# 1-Schematic_MiniMax_4bit.net
KiCad netlist of a schematic drawn in EasyEDA
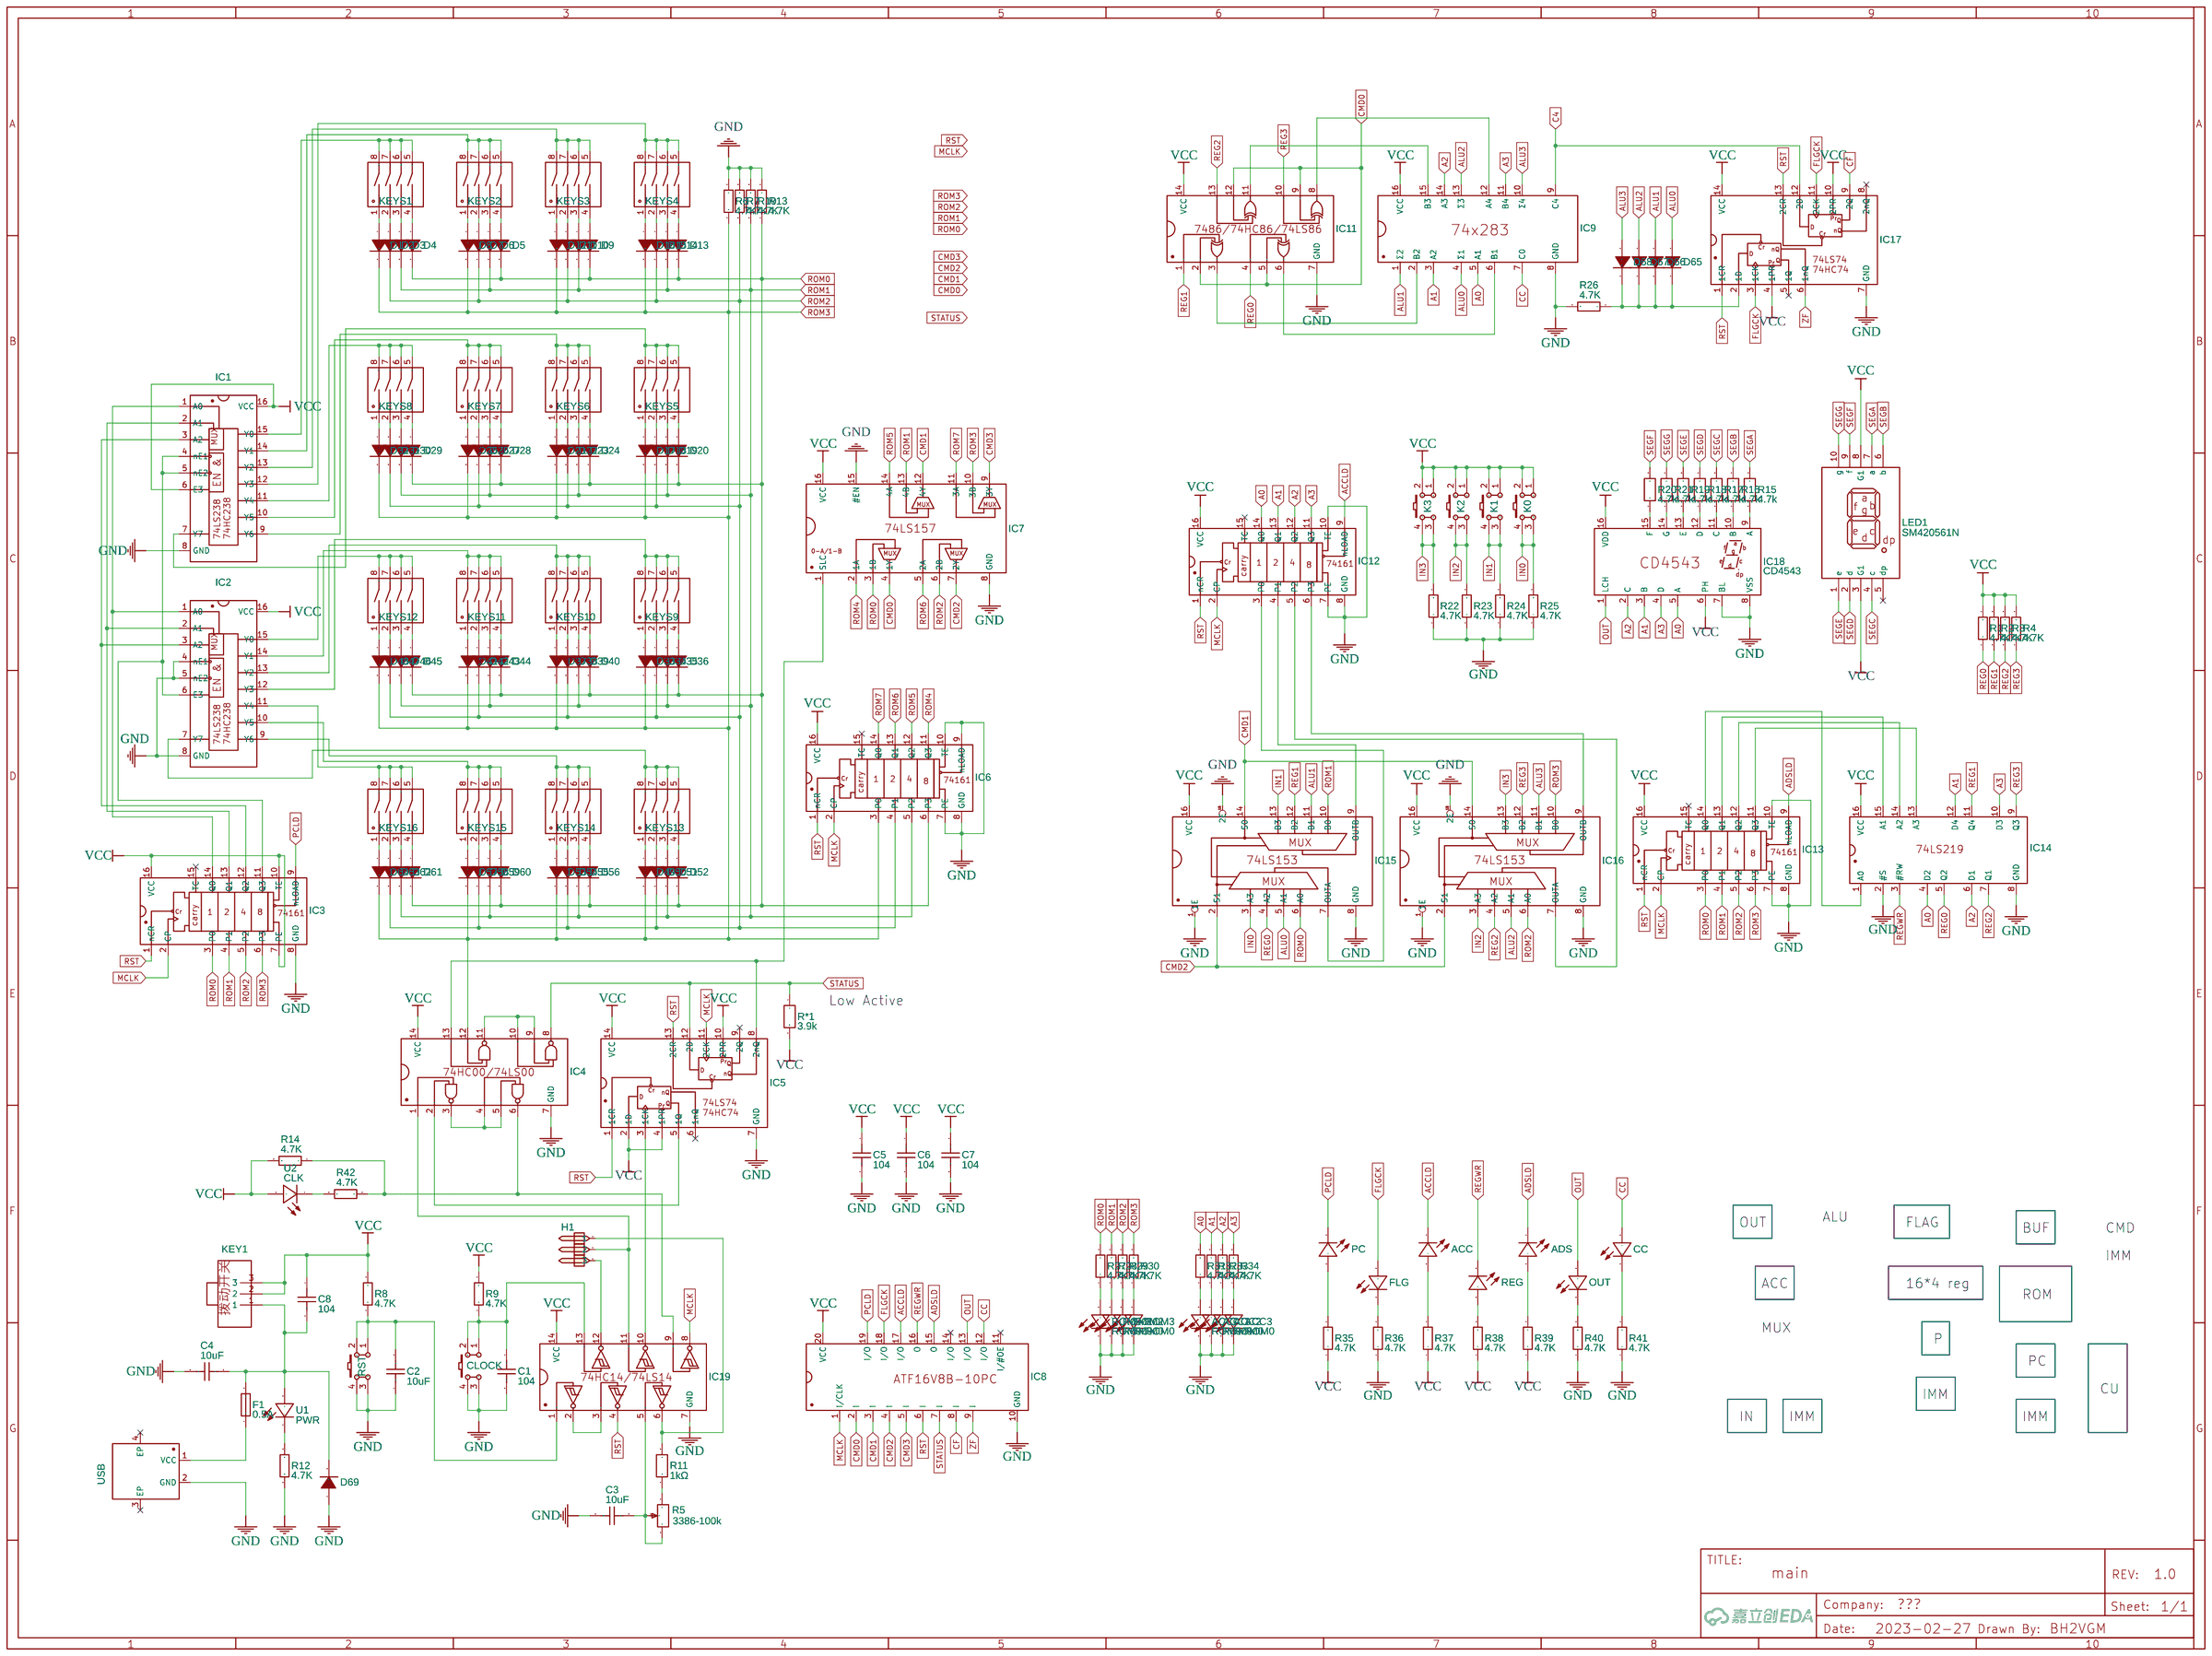
[diagram p0: schematic sheet]

(export (version "E")
  (design (tool "Eeschema 10.0.6"))
  (components
    (comp (ref "ACC")
      (value "ROM0")
      (fields
        (field (name "BOM_Manufacturer Part") "LED0805-1")
        (field (name "BOM_Supplier Part") "C9900006888")
      )
      (libsource (lib "") (part "LED0805-1_3"))
    )
    (comp (ref "ACC0")
      (value "ROM0")
      (fields
        (field (name "BOM_Manufacturer Part") "LED0805-1")
        (field (name "BOM_Supplier Part") "C9900006888")
      )
      (libsource (lib "") (part "LED0805-1_2"))
    )
    (comp (ref "ACC1")
      (value "ROM0")
      (fields
        (field (name "BOM_Manufacturer Part") "LED0805-1")
        (field (name "BOM_Supplier Part") "C9900006888")
      )
      (libsource (lib "") (part "LED0805-1_2"))
    )
    (comp (ref "ACC2")
      (value "ROM0")
      (fields
        (field (name "BOM_Manufacturer Part") "LED0805-1")
        (field (name "BOM_Supplier Part") "C9900006888")
      )
      (libsource (lib "") (part "LED0805-1_2"))
    )
    (comp (ref "ACC3")
      (value "ROM0")
      (fields
        (field (name "BOM_Manufacturer Part") "LED0805-1")
        (field (name "BOM_Supplier Part") "C9900006888")
      )
      (libsource (lib "") (part "LED0805-1_2"))
    )
    (comp (ref "ADS")
      (value "ROM0")
      (fields
        (field (name "BOM_Manufacturer Part") "LED0805-1")
        (field (name "BOM_Supplier Part") "C9900006888")
      )
      (libsource (lib "") (part "LED0805-1_1"))
    )
    (comp (ref "C1")
      (value "104")
      (fields
        (field (name "BOM_Manufacturer Part") "CC0805JRX7R7BB104")
        (field (name "BOM_Supplier Part") "C520082")
      )
      (libsource (lib "") (part "CC0805JRX7R7BB104"))
    )
    (comp (ref "C2")
      (value "10uF")
      (fields
        (field (name "BOM_Manufacturer Part") "C1206C225J5RECAUTO")
        (field (name "BOM_Supplier Part") "C1513220")
      )
      (libsource (lib "") (part "C1206C225J5RECAUTO_1"))
    )
    (comp (ref "C3")
      (value "10uF")
      (fields
        (field (name "BOM_Manufacturer Part") "C1206C225J5RECAUTO")
        (field (name "BOM_Supplier Part") "C1513220")
      )
      (libsource (lib "") (part "C1206C225J5RECAUTO_2"))
    )
    (comp (ref "C4")
      (value "10uF")
      (fields
        (field (name "BOM_Manufacturer Part") "C1206C225J5RECAUTO")
        (field (name "BOM_Supplier Part") "C1513220")
      )
      (libsource (lib "") (part "C1206C225J5RECAUTO"))
    )
    (comp (ref "C5")
      (value "104")
      (fields
        (field (name "BOM_Manufacturer Part") "CC0805JRX7R7BB104")
        (field (name "BOM_Supplier Part") "C520082")
      )
      (libsource (lib "") (part "CC0805JRX7R7BB104"))
    )
    (comp (ref "C6")
      (value "104")
      (fields
        (field (name "BOM_Manufacturer Part") "CC0805JRX7R7BB104")
        (field (name "BOM_Supplier Part") "C520082")
      )
      (libsource (lib "") (part "CC0805JRX7R7BB104"))
    )
    (comp (ref "C7")
      (value "104")
      (fields
        (field (name "BOM_Manufacturer Part") "CC0805JRX7R7BB104")
        (field (name "BOM_Supplier Part") "C520082")
      )
      (libsource (lib "") (part "CC0805JRX7R7BB104"))
    )
    (comp (ref "C8")
      (value "104")
      (fields
        (field (name "BOM_Manufacturer Part") "CC0805JRX7R7BB104")
        (field (name "BOM_Supplier Part") "C520082")
      )
      (libsource (lib "") (part "CC0805JRX7R7BB104"))
    )
    (comp (ref "CC")
      (value "ROM0")
      (fields
        (field (name "BOM_Manufacturer Part") "LED0805-1")
        (field (name "BOM_Supplier Part") "C9900006888")
      )
      (libsource (lib "") (part "LED0805-1_6"))
    )
    (comp (ref "CLOCK")
      (value "K4-6×6_TH")
      (fields
        (field (name "BOM_Manufacturer Part") "K2-1102DP-E4SW-04")
        (field (name "BOM_Supplier Part") "C136684")
      )
      (libsource (lib "") (part "K4-6×6_TH"))
    )
    (comp (ref "D1")
      (value "LL4148SG")
      (fields (field (name "BOM_Supplier Part") "C9900015421"))
      (libsource (lib "") (part "LL4148SG"))
    )
    (comp (ref "D2")
      (value "LL4148SG")
      (fields (field (name "BOM_Supplier Part") "C9900015421"))
      (libsource (lib "") (part "LL4148SG"))
    )
    (comp (ref "D3")
      (value "LL4148SG")
      (fields (field (name "BOM_Supplier Part") "C9900015421"))
      (libsource (lib "") (part "LL4148SG"))
    )
    (comp (ref "D4")
      (value "LL4148SG")
      (fields (field (name "BOM_Supplier Part") "C9900015421"))
      (libsource (lib "") (part "LL4148SG"))
    )
    (comp (ref "D5")
      (value "LL4148SG")
      (fields (field (name "BOM_Supplier Part") "C9900015421"))
      (libsource (lib "") (part "LL4148SG"))
    )
    (comp (ref "D6")
      (value "LL4148SG")
      (fields (field (name "BOM_Supplier Part") "C9900015421"))
      (libsource (lib "") (part "LL4148SG"))
    )
    (comp (ref "D7")
      (value "LL4148SG")
      (fields (field (name "BOM_Supplier Part") "C9900015421"))
      (libsource (lib "") (part "LL4148SG"))
    )
    (comp (ref "D8")
      (value "LL4148SG")
      (fields (field (name "BOM_Supplier Part") "C9900015421"))
      (libsource (lib "") (part "LL4148SG"))
    )
    (comp (ref "D9")
      (value "LL4148SG")
      (fields (field (name "BOM_Supplier Part") "C9900015421"))
      (libsource (lib "") (part "LL4148SG"))
    )
    (comp (ref "D10")
      (value "LL4148SG")
      (fields (field (name "BOM_Supplier Part") "C9900015421"))
      (libsource (lib "") (part "LL4148SG"))
    )
    (comp (ref "D11")
      (value "LL4148SG")
      (fields (field (name "BOM_Supplier Part") "C9900015421"))
      (libsource (lib "") (part "LL4148SG"))
    )
    (comp (ref "D12")
      (value "LL4148SG")
      (fields (field (name "BOM_Supplier Part") "C9900015421"))
      (libsource (lib "") (part "LL4148SG"))
    )
    (comp (ref "D13")
      (value "LL4148SG")
      (fields (field (name "BOM_Supplier Part") "C9900015421"))
      (libsource (lib "") (part "LL4148SG"))
    )
    (comp (ref "D14")
      (value "LL4148SG")
      (fields (field (name "BOM_Supplier Part") "C9900015421"))
      (libsource (lib "") (part "LL4148SG"))
    )
    (comp (ref "D15")
      (value "LL4148SG")
      (fields (field (name "BOM_Supplier Part") "C9900015421"))
      (libsource (lib "") (part "LL4148SG"))
    )
    (comp (ref "D16")
      (value "LL4148SG")
      (fields (field (name "BOM_Supplier Part") "C9900015421"))
      (libsource (lib "") (part "LL4148SG"))
    )
    (comp (ref "D17")
      (value "LL4148SG")
      (fields (field (name "BOM_Supplier Part") "C9900015421"))
      (libsource (lib "") (part "LL4148SG"))
    )
    (comp (ref "D18")
      (value "LL4148SG")
      (fields (field (name "BOM_Supplier Part") "C9900015421"))
      (libsource (lib "") (part "LL4148SG"))
    )
    (comp (ref "D19")
      (value "LL4148SG")
      (fields (field (name "BOM_Supplier Part") "C9900015421"))
      (libsource (lib "") (part "LL4148SG"))
    )
    (comp (ref "D20")
      (value "LL4148SG")
      (fields (field (name "BOM_Supplier Part") "C9900015421"))
      (libsource (lib "") (part "LL4148SG"))
    )
    (comp (ref "D21")
      (value "LL4148SG")
      (fields (field (name "BOM_Supplier Part") "C9900015421"))
      (libsource (lib "") (part "LL4148SG"))
    )
    (comp (ref "D22")
      (value "LL4148SG")
      (fields (field (name "BOM_Supplier Part") "C9900015421"))
      (libsource (lib "") (part "LL4148SG"))
    )
    (comp (ref "D23")
      (value "LL4148SG")
      (fields (field (name "BOM_Supplier Part") "C9900015421"))
      (libsource (lib "") (part "LL4148SG"))
    )
    (comp (ref "D24")
      (value "LL4148SG")
      (fields (field (name "BOM_Supplier Part") "C9900015421"))
      (libsource (lib "") (part "LL4148SG"))
    )
    (comp (ref "D25")
      (value "LL4148SG")
      (fields (field (name "BOM_Supplier Part") "C9900015421"))
      (libsource (lib "") (part "LL4148SG"))
    )
    (comp (ref "D26")
      (value "LL4148SG")
      (fields (field (name "BOM_Supplier Part") "C9900015421"))
      (libsource (lib "") (part "LL4148SG"))
    )
    (comp (ref "D27")
      (value "LL4148SG")
      (fields (field (name "BOM_Supplier Part") "C9900015421"))
      (libsource (lib "") (part "LL4148SG"))
    )
    (comp (ref "D28")
      (value "LL4148SG")
      (fields (field (name "BOM_Supplier Part") "C9900015421"))
      (libsource (lib "") (part "LL4148SG"))
    )
    (comp (ref "D29")
      (value "LL4148SG")
      (fields (field (name "BOM_Supplier Part") "C9900015421"))
      (libsource (lib "") (part "LL4148SG"))
    )
    (comp (ref "D30")
      (value "LL4148SG")
      (fields (field (name "BOM_Supplier Part") "C9900015421"))
      (libsource (lib "") (part "LL4148SG"))
    )
    (comp (ref "D31")
      (value "LL4148SG")
      (fields (field (name "BOM_Supplier Part") "C9900015421"))
      (libsource (lib "") (part "LL4148SG"))
    )
    (comp (ref "D32")
      (value "LL4148SG")
      (fields (field (name "BOM_Supplier Part") "C9900015421"))
      (libsource (lib "") (part "LL4148SG"))
    )
    (comp (ref "D33")
      (value "LL4148SG")
      (fields (field (name "BOM_Supplier Part") "C9900015421"))
      (libsource (lib "") (part "LL4148SG"))
    )
    (comp (ref "D34")
      (value "LL4148SG")
      (fields (field (name "BOM_Supplier Part") "C9900015421"))
      (libsource (lib "") (part "LL4148SG"))
    )
    (comp (ref "D35")
      (value "LL4148SG")
      (fields (field (name "BOM_Supplier Part") "C9900015421"))
      (libsource (lib "") (part "LL4148SG"))
    )
    (comp (ref "D36")
      (value "LL4148SG")
      (fields (field (name "BOM_Supplier Part") "C9900015421"))
      (libsource (lib "") (part "LL4148SG"))
    )
    (comp (ref "D37")
      (value "LL4148SG")
      (fields (field (name "BOM_Supplier Part") "C9900015421"))
      (libsource (lib "") (part "LL4148SG"))
    )
    (comp (ref "D38")
      (value "LL4148SG")
      (fields (field (name "BOM_Supplier Part") "C9900015421"))
      (libsource (lib "") (part "LL4148SG"))
    )
    (comp (ref "D39")
      (value "LL4148SG")
      (fields (field (name "BOM_Supplier Part") "C9900015421"))
      (libsource (lib "") (part "LL4148SG"))
    )
    (comp (ref "D40")
      (value "LL4148SG")
      (fields (field (name "BOM_Supplier Part") "C9900015421"))
      (libsource (lib "") (part "LL4148SG"))
    )
    (comp (ref "D41")
      (value "LL4148SG")
      (fields (field (name "BOM_Supplier Part") "C9900015421"))
      (libsource (lib "") (part "LL4148SG"))
    )
    (comp (ref "D42")
      (value "LL4148SG")
      (fields (field (name "BOM_Supplier Part") "C9900015421"))
      (libsource (lib "") (part "LL4148SG"))
    )
    (comp (ref "D43")
      (value "LL4148SG")
      (fields (field (name "BOM_Supplier Part") "C9900015421"))
      (libsource (lib "") (part "LL4148SG"))
    )
    (comp (ref "D44")
      (value "LL4148SG")
      (fields (field (name "BOM_Supplier Part") "C9900015421"))
      (libsource (lib "") (part "LL4148SG"))
    )
    (comp (ref "D45")
      (value "LL4148SG")
      (fields (field (name "BOM_Supplier Part") "C9900015421"))
      (libsource (lib "") (part "LL4148SG"))
    )
    (comp (ref "D46")
      (value "LL4148SG")
      (fields (field (name "BOM_Supplier Part") "C9900015421"))
      (libsource (lib "") (part "LL4148SG"))
    )
    (comp (ref "D47")
      (value "LL4148SG")
      (fields (field (name "BOM_Supplier Part") "C9900015421"))
      (libsource (lib "") (part "LL4148SG"))
    )
    (comp (ref "D48")
      (value "LL4148SG")
      (fields (field (name "BOM_Supplier Part") "C9900015421"))
      (libsource (lib "") (part "LL4148SG"))
    )
    (comp (ref "D49")
      (value "LL4148SG")
      (fields (field (name "BOM_Supplier Part") "C9900015421"))
      (libsource (lib "") (part "LL4148SG"))
    )
    (comp (ref "D50")
      (value "LL4148SG")
      (fields (field (name "BOM_Supplier Part") "C9900015421"))
      (libsource (lib "") (part "LL4148SG"))
    )
    (comp (ref "D51")
      (value "LL4148SG")
      (fields (field (name "BOM_Supplier Part") "C9900015421"))
      (libsource (lib "") (part "LL4148SG"))
    )
    (comp (ref "D52")
      (value "LL4148SG")
      (fields (field (name "BOM_Supplier Part") "C9900015421"))
      (libsource (lib "") (part "LL4148SG"))
    )
    (comp (ref "D53")
      (value "LL4148SG")
      (fields (field (name "BOM_Supplier Part") "C9900015421"))
      (libsource (lib "") (part "LL4148SG"))
    )
    (comp (ref "D54")
      (value "LL4148SG")
      (fields (field (name "BOM_Supplier Part") "C9900015421"))
      (libsource (lib "") (part "LL4148SG"))
    )
    (comp (ref "D55")
      (value "LL4148SG")
      (fields (field (name "BOM_Supplier Part") "C9900015421"))
      (libsource (lib "") (part "LL4148SG"))
    )
    (comp (ref "D56")
      (value "LL4148SG")
      (fields (field (name "BOM_Supplier Part") "C9900015421"))
      (libsource (lib "") (part "LL4148SG"))
    )
    (comp (ref "D57")
      (value "LL4148SG")
      (fields (field (name "BOM_Supplier Part") "C9900015421"))
      (libsource (lib "") (part "LL4148SG"))
    )
    (comp (ref "D58")
      (value "LL4148SG")
      (fields (field (name "BOM_Supplier Part") "C9900015421"))
      (libsource (lib "") (part "LL4148SG"))
    )
    (comp (ref "D59")
      (value "LL4148SG")
      (fields (field (name "BOM_Supplier Part") "C9900015421"))
      (libsource (lib "") (part "LL4148SG"))
    )
    (comp (ref "D60")
      (value "LL4148SG")
      (fields (field (name "BOM_Supplier Part") "C9900015421"))
      (libsource (lib "") (part "LL4148SG"))
    )
    (comp (ref "D61")
      (value "LL4148SG")
      (fields (field (name "BOM_Supplier Part") "C9900015421"))
      (libsource (lib "") (part "LL4148SG"))
    )
    (comp (ref "D62")
      (value "LL4148SG")
      (fields (field (name "BOM_Supplier Part") "C9900015421"))
      (libsource (lib "") (part "LL4148SG"))
    )
    (comp (ref "D63")
      (value "LL4148SG")
      (fields (field (name "BOM_Supplier Part") "C9900015421"))
      (libsource (lib "") (part "LL4148SG"))
    )
    (comp (ref "D64")
      (value "LL4148SG")
      (fields (field (name "BOM_Supplier Part") "C9900015421"))
      (libsource (lib "") (part "LL4148SG"))
    )
    (comp (ref "D65")
      (value "LL4148SG")
      (fields (field (name "BOM_Supplier Part") "C9900015421"))
      (libsource (lib "") (part "LL4148SG_1"))
    )
    (comp (ref "D66")
      (value "LL4148SG")
      (fields (field (name "BOM_Supplier Part") "C9900015421"))
      (libsource (lib "") (part "LL4148SG_1"))
    )
    (comp (ref "D67")
      (value "LL4148SG")
      (fields (field (name "BOM_Supplier Part") "C9900015421"))
      (libsource (lib "") (part "LL4148SG_1"))
    )
    (comp (ref "D68")
      (value "LL4148SG")
      (fields (field (name "BOM_Supplier Part") "C9900015421"))
      (libsource (lib "") (part "LL4148SG_1"))
    )
    (comp (ref "D69")
      (value "LL4148SG")
      (fields (field (name "BOM_Supplier Part") "C9900015421"))
      (libsource (lib "") (part "LL4148SG_2"))
    )
    (comp (ref "F1")
      (value "0.5A")
      (fields
        (field (name "BOM_Manufacturer Part") "1206L016WR")
        (field (name "BOM_Supplier Part") "C151161")
      )
      (libsource (lib "") (part "1206L016WR"))
    )
    (comp (ref "FLG")
      (value "ROM0")
      (fields
        (field (name "BOM_Manufacturer Part") "LED0805-1")
        (field (name "BOM_Supplier Part") "C9900006888")
      )
      (libsource (lib "") (part "LED0805-1_10"))
    )
    (comp (ref "H1")
      (value "排针V2_2.54_1X3")
      (fields
        (field (name "BOM_Manufacturer Part") "Header2.54mm 1*3P")
        (field (name "BOM_Supplier Part") "C49257")
      )
      (libsource (lib "") (part "排针V2_2.54_1X3"))
    )
    (comp (ref "IC1")
      (value "74238/74LS238/74HC238")
      (fields (field (name "BOM_Manufacturer Part") "74HC138T") (field (name "BOM_Supplier Part") "C2906781"))
      (libsource (lib "") (part "74238/74LS238/74HC238"))
    )
    (comp (ref "IC2")
      (value "74238/74LS238/74HC238")
      (fields (field (name "BOM_Manufacturer Part") "74HC138T") (field (name "BOM_Supplier Part") "C2906781"))
      (libsource (lib "") (part "74238/74LS238/74HC238"))
    )
    (comp (ref "IC3")
      (value "74161/74LS161/74HC161")
      (fields
        (field (name "BOM_Manufacturer Part") "CD74HC161E")
        (field (name "BOM_Supplier Part") "C1523311")
      )
      (libsource (lib "") (part "74161/74LS161/74HC161_1"))
    )
    (comp (ref "IC4")
      (value "7400/74LS00/74HC00")
      (fields (field (name "BOM_Manufacturer Part") "SN74HC00N") (field (name "BOM_Supplier Part") "C2902"))
      (libsource (lib "") (part "7400/74LS00/74HC00"))
    )
    (comp (ref "IC5")
      (value "7474/74LS74/74HC74")
      (fields (field (name "BOM_Manufacturer Part") "HD74HC74P") (field (name "BOM_Supplier Part") "C5275"))
      (libsource (lib "") (part "7474/74LS74/74HC74"))
    )
    (comp (ref "IC6")
      (value "74161/74LS161/74HC161")
      (fields
        (field (name "BOM_Manufacturer Part") "CD74HC161E")
        (field (name "BOM_Supplier Part") "C1523311")
      )
      (libsource (lib "") (part "74161/74LS161/74HC161"))
    )
    (comp (ref "IC7")
      (value "74157/74LS157/74HC157")
      (fields (field (name "BOM_Manufacturer Part") "SN74LS148N") (field (name "BOM_Supplier Part") "C81840"))
      (libsource (lib "") (part "74157/74LS157/74HC157"))
    )
    (comp (ref "IC8") (value "ATF16V8B") (libsource (lib "") (part "ATF16V8B")))
    (comp (ref "IC9") (value "74283/74LS283/74HC283") (libsource (lib "") (part "74283/74LS283/74HC283")))
    (comp (ref "IC11")
      (value "7486/74LS86/74HC86")
      (fields (field (name "BOM_Manufacturer Part") "SN74HC00N") (field (name "BOM_Supplier Part") "C2902"))
      (libsource (lib "") (part "7486/74LS86/74HC86"))
    )
    (comp (ref "IC12")
      (value "74161/74LS161/74HC161")
      (fields
        (field (name "BOM_Manufacturer Part") "CD74HC161E")
        (field (name "BOM_Supplier Part") "C1523311")
      )
      (libsource (lib "") (part "74161/74LS161/74HC161"))
    )
    (comp (ref "IC13")
      (value "74161/74LS161/74HC161")
      (fields
        (field (name "BOM_Manufacturer Part") "CD74HC161E")
        (field (name "BOM_Supplier Part") "C1523311")
      )
      (libsource (lib "") (part "74161/74LS161/74HC161"))
    )
    (comp (ref "IC14") (value "74LS219") (libsource (lib "") (part "74LS219")))
    (comp (ref "IC15")
      (value "74153/74LS153/74HC153")
      (fields (field (name "BOM_Manufacturer Part") "SN74LS148N") (field (name "BOM_Supplier Part") "C81840"))
      (libsource (lib "") (part "74153/74LS153/74HC153"))
    )
    (comp (ref "IC16")
      (value "74153/74LS153/74HC153")
      (fields (field (name "BOM_Manufacturer Part") "SN74LS148N") (field (name "BOM_Supplier Part") "C81840"))
      (libsource (lib "") (part "74153/74LS153/74HC153"))
    )
    (comp (ref "IC17")
      (value "7474/74LS74/74HC74")
      (fields (field (name "BOM_Manufacturer Part") "HD74HC74P") (field (name "BOM_Supplier Part") "C5275"))
      (libsource (lib "") (part "7474/74LS74/74HC74"))
    )
    (comp (ref "IC18") (value "CD4543") (libsource (lib "") (part "CD4543")))
    (comp (ref "IC19") (value "7414/74LS14/74HC14") (libsource (lib "") (part "7414/74LS14/74HC14")))
    (comp (ref "K0")
      (value "K4-6×6_TH")
      (fields
        (field (name "BOM_Manufacturer Part") "K2-1102DP-E4SW-04")
        (field (name "BOM_Supplier Part") "C136684")
      )
      (libsource (lib "") (part "K4-6×6_TH_1"))
    )
    (comp (ref "K1")
      (value "K4-6×6_TH")
      (fields
        (field (name "BOM_Manufacturer Part") "K2-1102DP-E4SW-04")
        (field (name "BOM_Supplier Part") "C136684")
      )
      (libsource (lib "") (part "K4-6×6_TH_1"))
    )
    (comp (ref "K2")
      (value "K4-6×6_TH")
      (fields
        (field (name "BOM_Manufacturer Part") "K2-1102DP-E4SW-04")
        (field (name "BOM_Supplier Part") "C136684")
      )
      (libsource (lib "") (part "K4-6×6_TH_1"))
    )
    (comp (ref "K3")
      (value "K4-6×6_TH")
      (fields
        (field (name "BOM_Manufacturer Part") "K2-1102DP-E4SW-04")
        (field (name "BOM_Supplier Part") "C136684")
      )
      (libsource (lib "") (part "K4-6×6_TH_1"))
    )
    (comp (ref "KEY1") (value "拨动开关2.54*3直插") (libsource (lib "") (part "拨动开关2.54*3直插")))
    (comp (ref "KEYS1") (value "2.54 插件4位拨码开关") (libsource (lib "") (part "2.54 插件4位拨码开关")))
    (comp (ref "KEYS2") (value "2.54 插件4位拨码开关") (libsource (lib "") (part "2.54 插件4位拨码开关")))
    (comp (ref "KEYS3") (value "2.54 插件4位拨码开关") (libsource (lib "") (part "2.54 插件4位拨码开关")))
    (comp (ref "KEYS4") (value "2.54 插件4位拨码开关") (libsource (lib "") (part "2.54 插件4位拨码开关")))
    (comp (ref "KEYS5") (value "2.54 插件4位拨码开关") (libsource (lib "") (part "2.54 插件4位拨码开关")))
    (comp (ref "KEYS6") (value "2.54 插件4位拨码开关") (libsource (lib "") (part "2.54 插件4位拨码开关")))
    (comp (ref "KEYS7") (value "2.54 插件4位拨码开关") (libsource (lib "") (part "2.54 插件4位拨码开关")))
    (comp (ref "KEYS8") (value "2.54 插件4位拨码开关") (libsource (lib "") (part "2.54 插件4位拨码开关")))
    (comp (ref "KEYS9") (value "2.54 插件4位拨码开关") (libsource (lib "") (part "2.54 插件4位拨码开关")))
    (comp (ref "KEYS10") (value "2.54 插件4位拨码开关") (libsource (lib "") (part "2.54 插件4位拨码开关")))
    (comp (ref "KEYS11") (value "2.54 插件4位拨码开关") (libsource (lib "") (part "2.54 插件4位拨码开关")))
    (comp (ref "KEYS12") (value "2.54 插件4位拨码开关") (libsource (lib "") (part "2.54 插件4位拨码开关")))
    (comp (ref "KEYS13") (value "2.54 插件4位拨码开关") (libsource (lib "") (part "2.54 插件4位拨码开关")))
    (comp (ref "KEYS14") (value "2.54 插件4位拨码开关") (libsource (lib "") (part "2.54 插件4位拨码开关")))
    (comp (ref "KEYS15") (value "2.54 插件4位拨码开关") (libsource (lib "") (part "2.54 插件4位拨码开关")))
    (comp (ref "KEYS16") (value "2.54 插件4位拨码开关") (libsource (lib "") (part "2.54 插件4位拨码开关")))
    (comp (ref "LED1")
      (value "SM420561N")
      (fields (field (name "BOM_Supplier Part") "C141367"))
      (libsource (lib "") (part "SM420561N"))
    )
    (comp (ref "OUT")
      (value "ROM0")
      (fields
        (field (name "BOM_Manufacturer Part") "LED0805-1")
        (field (name "BOM_Supplier Part") "C9900006888")
      )
      (libsource (lib "") (part "LED0805-1_5"))
    )
    (comp (ref "PC")
      (value "ROM0")
      (fields
        (field (name "BOM_Manufacturer Part") "LED0805-1")
        (field (name "BOM_Supplier Part") "C9900006888")
      )
      (libsource (lib "") (part "LED0805-1_8"))
    )
    (comp (ref "R*1")
      (value "3.9k")
      (fields
        (field (name "BOM_Manufacturer Part") "SCR0805F1K")
        (field (name "BOM_Supplier Part") "C3016664")
      )
      (libsource (lib "") (part "SCR0805F1K_1"))
    )
    (comp (ref "R1")
      (value "4.7K")
      (fields
        (field (name "BOM_Manufacturer Part") "RC0805JR-074K7L")
        (field (name "BOM_Supplier Part") "C105427")
      )
      (libsource (lib "") (part "RC0805JR-074K7L"))
    )
    (comp (ref "R2")
      (value "4.7K")
      (fields
        (field (name "BOM_Manufacturer Part") "RC0805JR-074K7L")
        (field (name "BOM_Supplier Part") "C105427")
      )
      (libsource (lib "") (part "RC0805JR-074K7L"))
    )
    (comp (ref "R3")
      (value "4.7K")
      (fields
        (field (name "BOM_Manufacturer Part") "RC0805JR-074K7L")
        (field (name "BOM_Supplier Part") "C105427")
      )
      (libsource (lib "") (part "RC0805JR-074K7L"))
    )
    (comp (ref "R4")
      (value "4.7K")
      (fields
        (field (name "BOM_Manufacturer Part") "RC0805JR-074K7L")
        (field (name "BOM_Supplier Part") "C105427")
      )
      (libsource (lib "") (part "RC0805JR-074K7L"))
    )
    (comp (ref "R5")
      (value "3386-100k")
      (fields (field (name "BOM_Manufacturer Part") "3386P-1-105") (field (name "BOM_Supplier Part") "C5038"))
      (libsource (lib "") (part "3386P-1-105"))
    )
    (comp (ref "R6")
      (value "4.7K")
      (fields
        (field (name "BOM_Manufacturer Part") "RC0805JR-074K7L")
        (field (name "BOM_Supplier Part") "C105427")
      )
      (libsource (lib "") (part "RC0805JR-074K7L"))
    )
    (comp (ref "R7")
      (value "4.7K")
      (fields
        (field (name "BOM_Manufacturer Part") "RC0805JR-074K7L")
        (field (name "BOM_Supplier Part") "C105427")
      )
      (libsource (lib "") (part "RC0805JR-074K7L"))
    )
    (comp (ref "R8")
      (value "4.7K")
      (fields
        (field (name "BOM_Manufacturer Part") "RC0805JR-074K7L")
        (field (name "BOM_Supplier Part") "C105427")
      )
      (libsource (lib "") (part "RC0805JR-074K7L"))
    )
    (comp (ref "R9")
      (value "4.7K")
      (fields
        (field (name "BOM_Manufacturer Part") "RC0805JR-074K7L")
        (field (name "BOM_Supplier Part") "C105427")
      )
      (libsource (lib "") (part "RC0805JR-074K7L"))
    )
    (comp (ref "R10")
      (value "4.7K")
      (fields
        (field (name "BOM_Manufacturer Part") "RC0805JR-074K7L")
        (field (name "BOM_Supplier Part") "C105427")
      )
      (libsource (lib "") (part "RC0805JR-074K7L"))
    )
    (comp (ref "R11")
      (value "1kΩ")
      (fields
        (field (name "BOM_Manufacturer Part") "SCR0805F1K")
        (field (name "BOM_Supplier Part") "C3016664")
      )
      (libsource (lib "") (part "SCR0805F1K"))
    )
    (comp (ref "R12")
      (value "4.7K")
      (fields
        (field (name "BOM_Manufacturer Part") "RC0805JR-074K7L")
        (field (name "BOM_Supplier Part") "C105427")
      )
      (libsource (lib "") (part "RC0805JR-074K7L"))
    )
    (comp (ref "R13")
      (value "4.7K")
      (fields
        (field (name "BOM_Manufacturer Part") "RC0805JR-074K7L")
        (field (name "BOM_Supplier Part") "C105427")
      )
      (libsource (lib "") (part "RC0805JR-074K7L"))
    )
    (comp (ref "R14")
      (value "4.7K")
      (fields
        (field (name "BOM_Manufacturer Part") "RC0805JR-074K7L")
        (field (name "BOM_Supplier Part") "C105427")
      )
      (libsource (lib "") (part "RC0805JR-074K7L_1"))
    )
    (comp (ref "R15")
      (value "4.7k")
      (fields
        (field (name "BOM_Manufacturer Part") "SCR0603J1K")
        (field (name "BOM_Supplier Part") "C3017736")
      )
      (libsource (lib "") (part "SCR0603J1K"))
    )
    (comp (ref "R16")
      (value "4.7k")
      (fields
        (field (name "BOM_Manufacturer Part") "SCR0603J1K")
        (field (name "BOM_Supplier Part") "C3017736")
      )
      (libsource (lib "") (part "SCR0603J1K"))
    )
    (comp (ref "R17")
      (value "4.7k")
      (fields
        (field (name "BOM_Manufacturer Part") "SCR0603J1K")
        (field (name "BOM_Supplier Part") "C3017736")
      )
      (libsource (lib "") (part "SCR0603J1K"))
    )
    (comp (ref "R18")
      (value "4.7k")
      (fields
        (field (name "BOM_Manufacturer Part") "SCR0603J1K")
        (field (name "BOM_Supplier Part") "C3017736")
      )
      (libsource (lib "") (part "SCR0603J1K"))
    )
    (comp (ref "R19")
      (value "4.7k")
      (fields
        (field (name "BOM_Manufacturer Part") "SCR0603J1K")
        (field (name "BOM_Supplier Part") "C3017736")
      )
      (libsource (lib "") (part "SCR0603J1K"))
    )
    (comp (ref "R20")
      (value "4.7k")
      (fields
        (field (name "BOM_Manufacturer Part") "SCR0603J1K")
        (field (name "BOM_Supplier Part") "C3017736")
      )
      (libsource (lib "") (part "SCR0603J1K"))
    )
    (comp (ref "R21")
      (value "4.7k")
      (fields
        (field (name "BOM_Manufacturer Part") "SCR0603J1K")
        (field (name "BOM_Supplier Part") "C3017736")
      )
      (libsource (lib "") (part "SCR0603J1K"))
    )
    (comp (ref "R22")
      (value "4.7K")
      (fields
        (field (name "BOM_Manufacturer Part") "RC0805JR-074K7L")
        (field (name "BOM_Supplier Part") "C105427")
      )
      (libsource (lib "") (part "RC0805JR-074K7L"))
    )
    (comp (ref "R23")
      (value "4.7K")
      (fields
        (field (name "BOM_Manufacturer Part") "RC0805JR-074K7L")
        (field (name "BOM_Supplier Part") "C105427")
      )
      (libsource (lib "") (part "RC0805JR-074K7L"))
    )
    (comp (ref "R24")
      (value "4.7K")
      (fields
        (field (name "BOM_Manufacturer Part") "RC0805JR-074K7L")
        (field (name "BOM_Supplier Part") "C105427")
      )
      (libsource (lib "") (part "RC0805JR-074K7L"))
    )
    (comp (ref "R25")
      (value "4.7K")
      (fields
        (field (name "BOM_Manufacturer Part") "RC0805JR-074K7L")
        (field (name "BOM_Supplier Part") "C105427")
      )
      (libsource (lib "") (part "RC0805JR-074K7L"))
    )
    (comp (ref "R26")
      (value "4.7K")
      (fields
        (field (name "BOM_Manufacturer Part") "RC0805JR-074K7L")
        (field (name "BOM_Supplier Part") "C105427")
      )
      (libsource (lib "") (part "RC0805JR-074K7L_1"))
    )
    (comp (ref "R27")
      (value "4.7K")
      (fields
        (field (name "BOM_Manufacturer Part") "RC0805JR-074K7L")
        (field (name "BOM_Supplier Part") "C105427")
      )
      (libsource (lib "") (part "RC0805JR-074K7L"))
    )
    (comp (ref "R28")
      (value "4.7K")
      (fields
        (field (name "BOM_Manufacturer Part") "RC0805JR-074K7L")
        (field (name "BOM_Supplier Part") "C105427")
      )
      (libsource (lib "") (part "RC0805JR-074K7L"))
    )
    (comp (ref "R29")
      (value "4.7K")
      (fields
        (field (name "BOM_Manufacturer Part") "RC0805JR-074K7L")
        (field (name "BOM_Supplier Part") "C105427")
      )
      (libsource (lib "") (part "RC0805JR-074K7L"))
    )
    (comp (ref "R30")
      (value "4.7K")
      (fields
        (field (name "BOM_Manufacturer Part") "RC0805JR-074K7L")
        (field (name "BOM_Supplier Part") "C105427")
      )
      (libsource (lib "") (part "RC0805JR-074K7L"))
    )
    (comp (ref "R31")
      (value "4.7K")
      (fields
        (field (name "BOM_Manufacturer Part") "RC0805JR-074K7L")
        (field (name "BOM_Supplier Part") "C105427")
      )
      (libsource (lib "") (part "RC0805JR-074K7L"))
    )
    (comp (ref "R32")
      (value "4.7K")
      (fields
        (field (name "BOM_Manufacturer Part") "RC0805JR-074K7L")
        (field (name "BOM_Supplier Part") "C105427")
      )
      (libsource (lib "") (part "RC0805JR-074K7L"))
    )
    (comp (ref "R33")
      (value "4.7K")
      (fields
        (field (name "BOM_Manufacturer Part") "RC0805JR-074K7L")
        (field (name "BOM_Supplier Part") "C105427")
      )
      (libsource (lib "") (part "RC0805JR-074K7L"))
    )
    (comp (ref "R34")
      (value "4.7K")
      (fields
        (field (name "BOM_Manufacturer Part") "RC0805JR-074K7L")
        (field (name "BOM_Supplier Part") "C105427")
      )
      (libsource (lib "") (part "RC0805JR-074K7L"))
    )
    (comp (ref "R35")
      (value "4.7K")
      (fields
        (field (name "BOM_Manufacturer Part") "RC0805JR-074K7L")
        (field (name "BOM_Supplier Part") "C105427")
      )
      (libsource (lib "") (part "RC0805JR-074K7L"))
    )
    (comp (ref "R36")
      (value "4.7K")
      (fields
        (field (name "BOM_Manufacturer Part") "RC0805JR-074K7L")
        (field (name "BOM_Supplier Part") "C105427")
      )
      (libsource (lib "") (part "RC0805JR-074K7L"))
    )
    (comp (ref "R37")
      (value "4.7K")
      (fields
        (field (name "BOM_Manufacturer Part") "RC0805JR-074K7L")
        (field (name "BOM_Supplier Part") "C105427")
      )
      (libsource (lib "") (part "RC0805JR-074K7L"))
    )
    (comp (ref "R38")
      (value "4.7K")
      (fields
        (field (name "BOM_Manufacturer Part") "RC0805JR-074K7L")
        (field (name "BOM_Supplier Part") "C105427")
      )
      (libsource (lib "") (part "RC0805JR-074K7L"))
    )
    (comp (ref "R39")
      (value "4.7K")
      (fields
        (field (name "BOM_Manufacturer Part") "RC0805JR-074K7L")
        (field (name "BOM_Supplier Part") "C105427")
      )
      (libsource (lib "") (part "RC0805JR-074K7L"))
    )
    (comp (ref "R40")
      (value "4.7K")
      (fields
        (field (name "BOM_Manufacturer Part") "RC0805JR-074K7L")
        (field (name "BOM_Supplier Part") "C105427")
      )
      (libsource (lib "") (part "RC0805JR-074K7L"))
    )
    (comp (ref "R41")
      (value "4.7K")
      (fields
        (field (name "BOM_Manufacturer Part") "RC0805JR-074K7L")
        (field (name "BOM_Supplier Part") "C105427")
      )
      (libsource (lib "") (part "RC0805JR-074K7L"))
    )
    (comp (ref "R42")
      (value "4.7K")
      (fields
        (field (name "BOM_Manufacturer Part") "RC0805JR-074K7L")
        (field (name "BOM_Supplier Part") "C105427")
      )
      (libsource (lib "") (part "RC0805JR-074K7L_1"))
    )
    (comp (ref "REG")
      (value "ROM0")
      (fields
        (field (name "BOM_Manufacturer Part") "LED0805-1")
        (field (name "BOM_Supplier Part") "C9900006888")
      )
      (libsource (lib "") (part "LED0805-1_7"))
    )
    (comp (ref "ROM0")
      (value "ROM0")
      (fields
        (field (name "BOM_Manufacturer Part") "LED0805-1")
        (field (name "BOM_Supplier Part") "C9900006888")
      )
      (libsource (lib "") (part "LED0805-1"))
    )
    (comp (ref "ROM1")
      (value "ROM0")
      (fields
        (field (name "BOM_Manufacturer Part") "LED0805-1")
        (field (name "BOM_Supplier Part") "C9900006888")
      )
      (libsource (lib "") (part "LED0805-1"))
    )
    (comp (ref "ROM2")
      (value "ROM0")
      (fields
        (field (name "BOM_Manufacturer Part") "LED0805-1")
        (field (name "BOM_Supplier Part") "C9900006888")
      )
      (libsource (lib "") (part "LED0805-1"))
    )
    (comp (ref "ROM3")
      (value "ROM0")
      (fields
        (field (name "BOM_Manufacturer Part") "LED0805-1")
        (field (name "BOM_Supplier Part") "C9900006888")
      )
      (libsource (lib "") (part "LED0805-1"))
    )
    (comp (ref "RST")
      (value "K4-6×6_TH")
      (fields
        (field (name "BOM_Manufacturer Part") "K2-1102DP-E4SW-04")
        (field (name "BOM_Supplier Part") "C136684")
      )
      (libsource (lib "") (part "K4-6×6_TH_2"))
    )
    (comp (ref "U1")
      (value "PWR")
      (fields
        (field (name "BOM_Manufacturer Part") "LED0805-1")
        (field (name "BOM_Supplier Part") "C9900006888")
      )
      (libsource (lib "") (part "LED0805-1_4"))
    )
    (comp (ref "U2")
      (value "CLK")
      (fields
        (field (name "BOM_Manufacturer Part") "LED0805-1")
        (field (name "BOM_Supplier Part") "C9900006888")
      )
      (libsource (lib "") (part "LED0805-1_9"))
    )
    (comp (ref "USB")
      (value "KH-TYPE-C-2P")
      (fields (field (name "BOM_Supplier Part") "C2919656"))
      (libsource (lib "") (part "KH-TYPE-C-2P"))
    )
  )
  (nets
    (net (code "1") (name "A0") (class "Default")
      (node (ref "IC12") (pin "14") (pinfunction "Q0_14") (pintype "unspecified"))
      (node (ref "IC14") (pin "4") (pinfunction "D2_4") (pintype "unspecified"))
      (node (ref "IC18") (pin "5") (pinfunction "A_5") (pintype "unspecified"))
      (node (ref "IC9") (pin "5") (pinfunction "A1_5") (pintype "unspecified"))
      (node (ref "R31") (pin "2") (pinfunction "2_2") (pintype "input"))
    )
    (net (code "2") (name "A1") (class "Default")
      (node (ref "IC12") (pin "13") (pinfunction "Q1_13") (pintype "unspecified"))
      (node (ref "IC14") (pin "12") (pinfunction "D4_12") (pintype "unspecified"))
      (node (ref "IC18") (pin "3") (pinfunction "B_3") (pintype "unspecified"))
      (node (ref "IC9") (pin "3") (pinfunction "A2_3") (pintype "unspecified"))
      (node (ref "R32") (pin "2") (pinfunction "2_2") (pintype "input"))
    )
    (net (code "3") (name "A2") (class "Default")
      (node (ref "IC12") (pin "12") (pinfunction "Q2_12") (pintype "unspecified"))
      (node (ref "IC14") (pin "6") (pinfunction "D1_6") (pintype "unspecified"))
      (node (ref "IC18") (pin "2") (pinfunction "C_2") (pintype "unspecified"))
      (node (ref "IC9") (pin "14") (pinfunction "A3_14") (pintype "unspecified"))
      (node (ref "R33") (pin "2") (pinfunction "2_2") (pintype "input"))
    )
    (net (code "4") (name "A3") (class "Default")
      (node (ref "IC12") (pin "11") (pinfunction "Q3_11") (pintype "unspecified"))
      (node (ref "IC14") (pin "10") (pinfunction "D3_10") (pintype "unspecified"))
      (node (ref "IC18") (pin "4") (pinfunction "D_4") (pintype "unspecified"))
      (node (ref "IC9") (pin "11") (pinfunction "B4_11") (pintype "unspecified"))
      (node (ref "R34") (pin "2") (pinfunction "2_2") (pintype "input"))
    )
    (net (code "5") (name "ACCLD") (class "Default")
      (node (ref "ACC") (pin "1") (pinfunction "-_1") (pintype "unspecified"))
      (node (ref "IC12") (pin "9") (pinfunction "nLOAD_9") (pintype "unspecified"))
      (node (ref "IC8") (pin "17") (pinfunction "I/O_17") (pintype "unspecified"))
    )
    (net (code "6") (name "ADSLD") (class "Default")
      (node (ref "ADS") (pin "1") (pinfunction "-_1") (pintype "unspecified"))
      (node (ref "IC13") (pin "9") (pinfunction "nLOAD_9") (pintype "unspecified"))
      (node (ref "IC8") (pin "15") (pinfunction "O_15") (pintype "unspecified"))
    )
    (net (code "7") (name "ALU0") (class "Default")
      (node (ref "D65") (pin "1") (pinfunction "A_1") (pintype "unspecified"))
      (node (ref "IC15") (pin "5") (pinfunction "A1_5") (pintype "unspecified"))
      (node (ref "IC9") (pin "4") (pinfunction "Σ1_4") (pintype "unspecified"))
    )
    (net (code "8") (name "ALU1") (class "Default")
      (node (ref "D66") (pin "1") (pinfunction "A_1") (pintype "unspecified"))
      (node (ref "IC15") (pin "11") (pinfunction "B1_11") (pintype "unspecified"))
      (node (ref "IC9") (pin "1") (pinfunction "Σ2_1") (pintype "unspecified"))
    )
    (net (code "9") (name "ALU2") (class "Default")
      (node (ref "D67") (pin "1") (pinfunction "A_1") (pintype "unspecified"))
      (node (ref "IC16") (pin "5") (pinfunction "A1_5") (pintype "unspecified"))
      (node (ref "IC9") (pin "13") (pinfunction "Σ3_13") (pintype "unspecified"))
    )
    (net (code "10") (name "ALU3") (class "Default")
      (node (ref "D68") (pin "1") (pinfunction "A_1") (pintype "unspecified"))
      (node (ref "IC16") (pin "11") (pinfunction "B1_11") (pintype "unspecified"))
      (node (ref "IC9") (pin "10") (pinfunction "Σ4_10") (pintype "unspecified"))
    )
    (net (code "11") (name "C4") (class "Default")
      (node (ref "IC17") (pin "12") (pinfunction "2D_12") (pintype "unspecified"))
      (node (ref "IC9") (pin "9") (pinfunction "C4_9") (pintype "unspecified"))
    )
    (net (code "12") (name "CC") (class "Default")
      (node (ref "CC") (pin "2") (pinfunction "+_2") (pintype "unspecified"))
      (node (ref "IC8") (pin "12") (pinfunction "I/O_12") (pintype "unspecified"))
      (node (ref "IC9") (pin "7") (pinfunction "C0_7") (pintype "unspecified"))
    )
    (net (code "13") (name "CF") (class "Default")
      (node (ref "IC17") (pin "9") (pinfunction "2Q_9") (pintype "unspecified"))
      (node (ref "IC8") (pin "8") (pinfunction "I_8") (pintype "unspecified"))
    )
    (net (code "14") (name "CMD0") (class "Default")
      (node (ref "IC11") (pin "12") (pinfunction "4A_12") (pintype "unspecified"))
      (node (ref "IC11") (pin "2") (pinfunction "1B_2") (pintype "unspecified"))
      (node (ref "IC11") (pin "5") (pinfunction "2B_5") (pintype "unspecified"))
      (node (ref "IC11") (pin "9") (pinfunction "3A_9") (pintype "unspecified"))
      (node (ref "IC7") (pin "4") (pinfunction "1Y_4") (pintype "unspecified"))
      (node (ref "IC8") (pin "2") (pinfunction "I_2") (pintype "unspecified"))
    )
    (net (code "15") (name "CMD1") (class "Default")
      (node (ref "IC15") (pin "14") (pinfunction "S0_14") (pintype "unspecified"))
      (node (ref "IC16") (pin "14") (pinfunction "S0_14") (pintype "unspecified"))
      (node (ref "IC7") (pin "12") (pinfunction "4Y_12") (pintype "unspecified"))
      (node (ref "IC8") (pin "3") (pinfunction "I_3") (pintype "unspecified"))
    )
    (net (code "16") (name "CMD2") (class "Default")
      (node (ref "IC15") (pin "2") (pinfunction "S1_2") (pintype "unspecified"))
      (node (ref "IC16") (pin "2") (pinfunction "S1_2") (pintype "unspecified"))
      (node (ref "IC7") (pin "7") (pinfunction "2Y_7") (pintype "unspecified"))
      (node (ref "IC8") (pin "4") (pinfunction "I_4") (pintype "unspecified"))
    )
    (net (code "17") (name "CMD3") (class "Default")
      (node (ref "IC7") (pin "9") (pinfunction "3Y_9") (pintype "unspecified"))
      (node (ref "IC8") (pin "5") (pinfunction "I_5") (pintype "unspecified"))
    )
    (net (code "18") (name "FLGCK") (class "Default")
      (node (ref "FLG") (pin "2") (pinfunction "+_2") (pintype "unspecified"))
      (node (ref "IC17") (pin "11") (pinfunction "2CK_11") (pintype "unspecified"))
      (node (ref "IC17") (pin "3") (pinfunction "1CK_3") (pintype "unspecified"))
      (node (ref "IC8") (pin "18") (pinfunction "I/O_18") (pintype "unspecified"))
    )
    (net (code "19") (name "GND") (class "Default")
      (node (ref "ACC0") (pin "1") (pinfunction "-_1") (pintype "unspecified"))
      (node (ref "ACC1") (pin "1") (pinfunction "-_1") (pintype "unspecified"))
      (node (ref "ACC2") (pin "1") (pinfunction "-_1") (pintype "unspecified"))
      (node (ref "ACC3") (pin "1") (pinfunction "-_1") (pintype "unspecified"))
      (node (ref "C1") (pin "2") (pinfunction "2_2") (pintype "unspecified"))
      (node (ref "C2") (pin "1") (pinfunction "1_1") (pintype "unspecified"))
      (node (ref "C3") (pin "1") (pinfunction "1_1") (pintype "unspecified"))
      (node (ref "C4") (pin "2") (pinfunction "2_2") (pintype "unspecified"))
      (node (ref "C5") (pin "2") (pinfunction "2_2") (pintype "unspecified"))
      (node (ref "C6") (pin "2") (pinfunction "2_2") (pintype "unspecified"))
      (node (ref "C7") (pin "2") (pinfunction "2_2") (pintype "unspecified"))
      (node (ref "CLOCK") (pin "3") (pinfunction "3_3") (pintype "unspecified"))
      (node (ref "CLOCK") (pin "4") (pinfunction "4_4") (pintype "unspecified"))
      (node (ref "D69") (pin "1") (pinfunction "A_1") (pintype "unspecified"))
      (node (ref "IC1") (pin "8") (pinfunction "GND_8") (pintype "unspecified"))
      (node (ref "IC11") (pin "7") (pinfunction "GND_7") (pintype "unspecified"))
      (node (ref "IC12") (pin "10") (pinfunction "TE_10") (pintype "unspecified"))
      (node (ref "IC12") (pin "7") (pinfunction "PE_7") (pintype "unspecified"))
      (node (ref "IC12") (pin "8") (pinfunction "GND_8") (pintype "unspecified"))
      (node (ref "IC13") (pin "10") (pinfunction "TE_10") (pintype "unspecified"))
      (node (ref "IC13") (pin "7") (pinfunction "PE_7") (pintype "unspecified"))
      (node (ref "IC13") (pin "8") (pinfunction "GND_8") (pintype "unspecified"))
      (node (ref "IC14") (pin "2") (pinfunction "#S_2") (pintype "unspecified"))
      (node (ref "IC14") (pin "8") (pinfunction "GND_8") (pintype "unspecified"))
      (node (ref "IC15") (pin "1") (pinfunction "1E_1") (pintype "unspecified"))
      (node (ref "IC15") (pin "15") (pinfunction "2E_15") (pintype "unspecified"))
      (node (ref "IC15") (pin "8") (pinfunction "GND_8") (pintype "unspecified"))
      (node (ref "IC16") (pin "1") (pinfunction "1E_1") (pintype "unspecified"))
      (node (ref "IC16") (pin "15") (pinfunction "2E_15") (pintype "unspecified"))
      (node (ref "IC16") (pin "8") (pinfunction "GND_8") (pintype "unspecified"))
      (node (ref "IC17") (pin "7") (pinfunction "GND_7") (pintype "unspecified"))
      (node (ref "IC18") (pin "7") (pinfunction "BL_7") (pintype "unspecified"))
      (node (ref "IC18") (pin "8") (pinfunction "VSS_8") (pintype "unspecified"))
      (node (ref "IC19") (pin "7") (pinfunction "GND_7") (pintype "unspecified"))
      (node (ref "IC2") (pin "4") (pinfunction "nE1_4") (pintype "unspecified"))
      (node (ref "IC2") (pin "5") (pinfunction "nE2_5") (pintype "unspecified"))
      (node (ref "IC2") (pin "8") (pinfunction "GND_8") (pintype "unspecified"))
      (node (ref "IC3") (pin "8") (pinfunction "GND_8") (pintype "unspecified"))
      (node (ref "IC4") (pin "7") (pinfunction "GND_7") (pintype "unspecified"))
      (node (ref "IC5") (pin "7") (pinfunction "GND_7") (pintype "unspecified"))
      (node (ref "IC6") (pin "10") (pinfunction "TE_10") (pintype "unspecified"))
      (node (ref "IC6") (pin "7") (pinfunction "PE_7") (pintype "unspecified"))
      (node (ref "IC6") (pin "8") (pinfunction "GND_8") (pintype "unspecified"))
      (node (ref "IC6") (pin "9") (pinfunction "nLOAD_9") (pintype "unspecified"))
      (node (ref "IC7") (pin "15") (pinfunction "#EN_15") (pintype "unspecified"))
      (node (ref "IC7") (pin "8") (pinfunction "GND_8") (pintype "unspecified"))
      (node (ref "IC8") (pin "10") (pinfunction "GND_10") (pintype "unspecified"))
      (node (ref "IC9") (pin "8") (pinfunction "GND_8") (pintype "unspecified"))
      (node (ref "R10") (pin "2") (pinfunction "2_2") (pintype "input"))
      (node (ref "R12") (pin "1") (pinfunction "1_1") (pintype "input"))
      (node (ref "R13") (pin "2") (pinfunction "2_2") (pintype "input"))
      (node (ref "R22") (pin "1") (pinfunction "1_1") (pintype "input"))
      (node (ref "R23") (pin "1") (pinfunction "1_1") (pintype "input"))
      (node (ref "R24") (pin "1") (pinfunction "1_1") (pintype "input"))
      (node (ref "R25") (pin "1") (pinfunction "1_1") (pintype "input"))
      (node (ref "R26") (pin "2") (pinfunction "2_2") (pintype "input"))
      (node (ref "R36") (pin "1") (pinfunction "1_1") (pintype "input"))
      (node (ref "R40") (pin "1") (pinfunction "1_1") (pintype "input"))
      (node (ref "R41") (pin "1") (pinfunction "1_1") (pintype "input"))
      (node (ref "R6") (pin "2") (pinfunction "2_2") (pintype "input"))
      (node (ref "R7") (pin "2") (pinfunction "2_2") (pintype "input"))
      (node (ref "ROM0") (pin "1") (pinfunction "-_1") (pintype "unspecified"))
      (node (ref "ROM1") (pin "1") (pinfunction "-_1") (pintype "unspecified"))
      (node (ref "ROM2") (pin "1") (pinfunction "-_1") (pintype "unspecified"))
      (node (ref "ROM3") (pin "1") (pinfunction "-_1") (pintype "unspecified"))
      (node (ref "RST") (pin "3") (pinfunction "3_3") (pintype "unspecified"))
      (node (ref "RST") (pin "4") (pinfunction "4_4") (pintype "unspecified"))
      (node (ref "USB") (pin "2") (pinfunction "GND_2") (pintype "unspecified"))
    )
    (net (code "20") (name "IN0") (class "Default")
      (node (ref "IC15") (pin "3") (pinfunction "A3_3") (pintype "unspecified"))
      (node (ref "K0") (pin "3") (pinfunction "3_3") (pintype "unspecified"))
      (node (ref "K0") (pin "4") (pinfunction "4_4") (pintype "unspecified"))
      (node (ref "R25") (pin "2") (pinfunction "2_2") (pintype "input"))
    )
    (net (code "21") (name "IN1") (class "Default")
      (node (ref "IC15") (pin "13") (pinfunction "B3_13") (pintype "unspecified"))
      (node (ref "K1") (pin "3") (pinfunction "3_3") (pintype "unspecified"))
      (node (ref "K1") (pin "4") (pinfunction "4_4") (pintype "unspecified"))
      (node (ref "R24") (pin "2") (pinfunction "2_2") (pintype "input"))
    )
    (net (code "22") (name "IN2") (class "Default")
      (node (ref "IC16") (pin "3") (pinfunction "A3_3") (pintype "unspecified"))
      (node (ref "K2") (pin "3") (pinfunction "3_3") (pintype "unspecified"))
      (node (ref "K2") (pin "4") (pinfunction "4_4") (pintype "unspecified"))
      (node (ref "R23") (pin "2") (pinfunction "2_2") (pintype "input"))
    )
    (net (code "23") (name "IN3") (class "Default")
      (node (ref "IC16") (pin "13") (pinfunction "B3_13") (pintype "unspecified"))
      (node (ref "K3") (pin "3") (pinfunction "3_3") (pintype "unspecified"))
      (node (ref "K3") (pin "4") (pinfunction "4_4") (pintype "unspecified"))
      (node (ref "R22") (pin "2") (pinfunction "2_2") (pintype "input"))
    )
    (net (code "24") (name "MCLK") (class "Default")
      (node (ref "IC12") (pin "2") (pinfunction "CP_2") (pintype "unspecified"))
      (node (ref "IC13") (pin "2") (pinfunction "CP_2") (pintype "unspecified"))
      (node (ref "IC19") (pin "8") (pinfunction "6Y_8") (pintype "unspecified"))
      (node (ref "IC3") (pin "2") (pinfunction "CP_2") (pintype "unspecified"))
      (node (ref "IC5") (pin "11") (pinfunction "2CK_11") (pintype "unspecified"))
      (node (ref "IC6") (pin "2") (pinfunction "CP_2") (pintype "unspecified"))
      (node (ref "IC8") (pin "1") (pinfunction "I/CLK_1") (pintype "unspecified"))
    )
    (net (code "25") (name "Net-(ACC-+)") (class "Default")
      (node (ref "ACC") (pin "2") (pinfunction "+_2") (pintype "unspecified"))
      (node (ref "R37") (pin "2") (pinfunction "2_2") (pintype "input"))
    )
    (net (code "26") (name "Net-(ACC0-+)") (class "Default")
      (node (ref "ACC0") (pin "2") (pinfunction "+_2") (pintype "unspecified"))
      (node (ref "R31") (pin "1") (pinfunction "1_1") (pintype "input"))
    )
    (net (code "27") (name "Net-(ACC1-+)") (class "Default")
      (node (ref "ACC1") (pin "2") (pinfunction "+_2") (pintype "unspecified"))
      (node (ref "R32") (pin "1") (pinfunction "1_1") (pintype "input"))
    )
    (net (code "28") (name "Net-(ACC2-+)") (class "Default")
      (node (ref "ACC2") (pin "2") (pinfunction "+_2") (pintype "unspecified"))
      (node (ref "R33") (pin "1") (pinfunction "1_1") (pintype "input"))
    )
    (net (code "29") (name "Net-(ACC3-+)") (class "Default")
      (node (ref "ACC3") (pin "2") (pinfunction "+_2") (pintype "unspecified"))
      (node (ref "R34") (pin "1") (pinfunction "1_1") (pintype "input"))
    )
    (net (code "30") (name "Net-(ADS-+)") (class "Default")
      (node (ref "ADS") (pin "2") (pinfunction "+_2") (pintype "unspecified"))
      (node (ref "R39") (pin "2") (pinfunction "2_2") (pintype "input"))
    )
    (net (code "31") (name "Net-(CC--)") (class "Default")
      (node (ref "CC") (pin "1") (pinfunction "-_1") (pintype "unspecified"))
      (node (ref "R41") (pin "2") (pinfunction "2_2") (pintype "input"))
    )
    (net (code "32") (name "Net-(D1-A)") (class "Default")
      (node (ref "D1") (pin "1") (pinfunction "A_1") (pintype "unspecified"))
      (node (ref "KEYS1") (pin "1") (pinfunction "1_1") (pintype "unspecified"))
    )
    (net (code "33") (name "Net-(D2-A)") (class "Default")
      (node (ref "D2") (pin "1") (pinfunction "A_1") (pintype "unspecified"))
      (node (ref "KEYS1") (pin "2") (pinfunction "2_2") (pintype "unspecified"))
    )
    (net (code "34") (name "Net-(D3-A)") (class "Default")
      (node (ref "D3") (pin "1") (pinfunction "A_1") (pintype "unspecified"))
      (node (ref "KEYS1") (pin "3") (pinfunction "3_3") (pintype "unspecified"))
    )
    (net (code "35") (name "Net-(D4-A)") (class "Default")
      (node (ref "D4") (pin "1") (pinfunction "A_1") (pintype "unspecified"))
      (node (ref "KEYS1") (pin "4") (pinfunction "4_4") (pintype "unspecified"))
    )
    (net (code "36") (name "Net-(D5-A)") (class "Default")
      (node (ref "D5") (pin "1") (pinfunction "A_1") (pintype "unspecified"))
      (node (ref "KEYS2") (pin "4") (pinfunction "4_4") (pintype "unspecified"))
    )
    (net (code "37") (name "Net-(D6-A)") (class "Default")
      (node (ref "D6") (pin "1") (pinfunction "A_1") (pintype "unspecified"))
      (node (ref "KEYS2") (pin "3") (pinfunction "3_3") (pintype "unspecified"))
    )
    (net (code "38") (name "Net-(D7-A)") (class "Default")
      (node (ref "D7") (pin "1") (pinfunction "A_1") (pintype "unspecified"))
      (node (ref "KEYS2") (pin "2") (pinfunction "2_2") (pintype "unspecified"))
    )
    (net (code "39") (name "Net-(D8-A)") (class "Default")
      (node (ref "D8") (pin "1") (pinfunction "A_1") (pintype "unspecified"))
      (node (ref "KEYS2") (pin "1") (pinfunction "1_1") (pintype "unspecified"))
    )
    (net (code "40") (name "Net-(D9-A)") (class "Default")
      (node (ref "D9") (pin "1") (pinfunction "A_1") (pintype "unspecified"))
      (node (ref "KEYS3") (pin "4") (pinfunction "4_4") (pintype "unspecified"))
    )
    (net (code "41") (name "Net-(D10-A)") (class "Default")
      (node (ref "D10") (pin "1") (pinfunction "A_1") (pintype "unspecified"))
      (node (ref "KEYS3") (pin "3") (pinfunction "3_3") (pintype "unspecified"))
    )
    (net (code "42") (name "Net-(D11-A)") (class "Default")
      (node (ref "D11") (pin "1") (pinfunction "A_1") (pintype "unspecified"))
      (node (ref "KEYS3") (pin "2") (pinfunction "2_2") (pintype "unspecified"))
    )
    (net (code "43") (name "Net-(D12-A)") (class "Default")
      (node (ref "D12") (pin "1") (pinfunction "A_1") (pintype "unspecified"))
      (node (ref "KEYS3") (pin "1") (pinfunction "1_1") (pintype "unspecified"))
    )
    (net (code "44") (name "Net-(D13-A)") (class "Default")
      (node (ref "D13") (pin "1") (pinfunction "A_1") (pintype "unspecified"))
      (node (ref "KEYS4") (pin "4") (pinfunction "4_4") (pintype "unspecified"))
    )
    (net (code "45") (name "Net-(D14-A)") (class "Default")
      (node (ref "D14") (pin "1") (pinfunction "A_1") (pintype "unspecified"))
      (node (ref "KEYS4") (pin "3") (pinfunction "3_3") (pintype "unspecified"))
    )
    (net (code "46") (name "Net-(D15-A)") (class "Default")
      (node (ref "D15") (pin "1") (pinfunction "A_1") (pintype "unspecified"))
      (node (ref "KEYS4") (pin "2") (pinfunction "2_2") (pintype "unspecified"))
    )
    (net (code "47") (name "Net-(D16-A)") (class "Default")
      (node (ref "D16") (pin "1") (pinfunction "A_1") (pintype "unspecified"))
      (node (ref "KEYS4") (pin "1") (pinfunction "1_1") (pintype "unspecified"))
    )
    (net (code "48") (name "Net-(D17-A)") (class "Default")
      (node (ref "D17") (pin "1") (pinfunction "A_1") (pintype "unspecified"))
      (node (ref "KEYS5") (pin "1") (pinfunction "1_1") (pintype "unspecified"))
    )
    (net (code "49") (name "Net-(D18-A)") (class "Default")
      (node (ref "D18") (pin "1") (pinfunction "A_1") (pintype "unspecified"))
      (node (ref "KEYS5") (pin "2") (pinfunction "2_2") (pintype "unspecified"))
    )
    (net (code "50") (name "Net-(D19-A)") (class "Default")
      (node (ref "D19") (pin "1") (pinfunction "A_1") (pintype "unspecified"))
      (node (ref "KEYS5") (pin "3") (pinfunction "3_3") (pintype "unspecified"))
    )
    (net (code "51") (name "Net-(D20-A)") (class "Default")
      (node (ref "D20") (pin "1") (pinfunction "A_1") (pintype "unspecified"))
      (node (ref "KEYS5") (pin "4") (pinfunction "4_4") (pintype "unspecified"))
    )
    (net (code "52") (name "Net-(D21-A)") (class "Default")
      (node (ref "D21") (pin "1") (pinfunction "A_1") (pintype "unspecified"))
      (node (ref "KEYS6") (pin "1") (pinfunction "1_1") (pintype "unspecified"))
    )
    (net (code "53") (name "Net-(D22-A)") (class "Default")
      (node (ref "D22") (pin "1") (pinfunction "A_1") (pintype "unspecified"))
      (node (ref "KEYS6") (pin "2") (pinfunction "2_2") (pintype "unspecified"))
    )
    (net (code "54") (name "Net-(D23-A)") (class "Default")
      (node (ref "D23") (pin "1") (pinfunction "A_1") (pintype "unspecified"))
      (node (ref "KEYS6") (pin "3") (pinfunction "3_3") (pintype "unspecified"))
    )
    (net (code "55") (name "Net-(D24-A)") (class "Default")
      (node (ref "D24") (pin "1") (pinfunction "A_1") (pintype "unspecified"))
      (node (ref "KEYS6") (pin "4") (pinfunction "4_4") (pintype "unspecified"))
    )
    (net (code "56") (name "Net-(D25-A)") (class "Default")
      (node (ref "D25") (pin "1") (pinfunction "A_1") (pintype "unspecified"))
      (node (ref "KEYS7") (pin "1") (pinfunction "1_1") (pintype "unspecified"))
    )
    (net (code "57") (name "Net-(D26-A)") (class "Default")
      (node (ref "D26") (pin "1") (pinfunction "A_1") (pintype "unspecified"))
      (node (ref "KEYS7") (pin "2") (pinfunction "2_2") (pintype "unspecified"))
    )
    (net (code "58") (name "Net-(D27-A)") (class "Default")
      (node (ref "D27") (pin "1") (pinfunction "A_1") (pintype "unspecified"))
      (node (ref "KEYS7") (pin "3") (pinfunction "3_3") (pintype "unspecified"))
    )
    (net (code "59") (name "Net-(D28-A)") (class "Default")
      (node (ref "D28") (pin "1") (pinfunction "A_1") (pintype "unspecified"))
      (node (ref "KEYS7") (pin "4") (pinfunction "4_4") (pintype "unspecified"))
    )
    (net (code "60") (name "Net-(D29-A)") (class "Default")
      (node (ref "D29") (pin "1") (pinfunction "A_1") (pintype "unspecified"))
      (node (ref "KEYS8") (pin "4") (pinfunction "4_4") (pintype "unspecified"))
    )
    (net (code "61") (name "Net-(D30-A)") (class "Default")
      (node (ref "D30") (pin "1") (pinfunction "A_1") (pintype "unspecified"))
      (node (ref "KEYS8") (pin "3") (pinfunction "3_3") (pintype "unspecified"))
    )
    (net (code "62") (name "Net-(D31-A)") (class "Default")
      (node (ref "D31") (pin "1") (pinfunction "A_1") (pintype "unspecified"))
      (node (ref "KEYS8") (pin "2") (pinfunction "2_2") (pintype "unspecified"))
    )
    (net (code "63") (name "Net-(D32-A)") (class "Default")
      (node (ref "D32") (pin "1") (pinfunction "A_1") (pintype "unspecified"))
      (node (ref "KEYS8") (pin "1") (pinfunction "1_1") (pintype "unspecified"))
    )
    (net (code "64") (name "Net-(D33-A)") (class "Default")
      (node (ref "D33") (pin "1") (pinfunction "A_1") (pintype "unspecified"))
      (node (ref "KEYS9") (pin "1") (pinfunction "1_1") (pintype "unspecified"))
    )
    (net (code "65") (name "Net-(D34-A)") (class "Default")
      (node (ref "D34") (pin "1") (pinfunction "A_1") (pintype "unspecified"))
      (node (ref "KEYS9") (pin "2") (pinfunction "2_2") (pintype "unspecified"))
    )
    (net (code "66") (name "Net-(D35-A)") (class "Default")
      (node (ref "D35") (pin "1") (pinfunction "A_1") (pintype "unspecified"))
      (node (ref "KEYS9") (pin "3") (pinfunction "3_3") (pintype "unspecified"))
    )
    (net (code "67") (name "Net-(D36-A)") (class "Default")
      (node (ref "D36") (pin "1") (pinfunction "A_1") (pintype "unspecified"))
      (node (ref "KEYS9") (pin "4") (pinfunction "4_4") (pintype "unspecified"))
    )
    (net (code "68") (name "Net-(D37-A)") (class "Default")
      (node (ref "D37") (pin "1") (pinfunction "A_1") (pintype "unspecified"))
      (node (ref "KEYS10") (pin "1") (pinfunction "1_1") (pintype "unspecified"))
    )
    (net (code "69") (name "Net-(D38-A)") (class "Default")
      (node (ref "D38") (pin "1") (pinfunction "A_1") (pintype "unspecified"))
      (node (ref "KEYS10") (pin "2") (pinfunction "2_2") (pintype "unspecified"))
    )
    (net (code "70") (name "Net-(D39-A)") (class "Default")
      (node (ref "D39") (pin "1") (pinfunction "A_1") (pintype "unspecified"))
      (node (ref "KEYS10") (pin "3") (pinfunction "3_3") (pintype "unspecified"))
    )
    (net (code "71") (name "Net-(D40-A)") (class "Default")
      (node (ref "D40") (pin "1") (pinfunction "A_1") (pintype "unspecified"))
      (node (ref "KEYS10") (pin "4") (pinfunction "4_4") (pintype "unspecified"))
    )
    (net (code "72") (name "Net-(D41-A)") (class "Default")
      (node (ref "D41") (pin "1") (pinfunction "A_1") (pintype "unspecified"))
      (node (ref "KEYS11") (pin "1") (pinfunction "1_1") (pintype "unspecified"))
    )
    (net (code "73") (name "Net-(D42-A)") (class "Default")
      (node (ref "D42") (pin "1") (pinfunction "A_1") (pintype "unspecified"))
      (node (ref "KEYS11") (pin "2") (pinfunction "2_2") (pintype "unspecified"))
    )
    (net (code "74") (name "Net-(D43-A)") (class "Default")
      (node (ref "D43") (pin "1") (pinfunction "A_1") (pintype "unspecified"))
      (node (ref "KEYS11") (pin "3") (pinfunction "3_3") (pintype "unspecified"))
    )
    (net (code "75") (name "Net-(D44-A)") (class "Default")
      (node (ref "D44") (pin "1") (pinfunction "A_1") (pintype "unspecified"))
      (node (ref "KEYS11") (pin "4") (pinfunction "4_4") (pintype "unspecified"))
    )
    (net (code "76") (name "Net-(D45-A)") (class "Default")
      (node (ref "D45") (pin "1") (pinfunction "A_1") (pintype "unspecified"))
      (node (ref "KEYS12") (pin "4") (pinfunction "4_4") (pintype "unspecified"))
    )
    (net (code "77") (name "Net-(D46-A)") (class "Default")
      (node (ref "D46") (pin "1") (pinfunction "A_1") (pintype "unspecified"))
      (node (ref "KEYS12") (pin "3") (pinfunction "3_3") (pintype "unspecified"))
    )
    (net (code "78") (name "Net-(D47-A)") (class "Default")
      (node (ref "D47") (pin "1") (pinfunction "A_1") (pintype "unspecified"))
      (node (ref "KEYS12") (pin "2") (pinfunction "2_2") (pintype "unspecified"))
    )
    (net (code "79") (name "Net-(D48-A)") (class "Default")
      (node (ref "D48") (pin "1") (pinfunction "A_1") (pintype "unspecified"))
      (node (ref "KEYS12") (pin "1") (pinfunction "1_1") (pintype "unspecified"))
    )
    (net (code "80") (name "Net-(D49-A)") (class "Default")
      (node (ref "D49") (pin "1") (pinfunction "A_1") (pintype "unspecified"))
      (node (ref "KEYS13") (pin "1") (pinfunction "1_1") (pintype "unspecified"))
    )
    (net (code "81") (name "Net-(D50-A)") (class "Default")
      (node (ref "D50") (pin "1") (pinfunction "A_1") (pintype "unspecified"))
      (node (ref "KEYS13") (pin "2") (pinfunction "2_2") (pintype "unspecified"))
    )
    (net (code "82") (name "Net-(D51-A)") (class "Default")
      (node (ref "D51") (pin "1") (pinfunction "A_1") (pintype "unspecified"))
      (node (ref "KEYS13") (pin "3") (pinfunction "3_3") (pintype "unspecified"))
    )
    (net (code "83") (name "Net-(D52-A)") (class "Default")
      (node (ref "D52") (pin "1") (pinfunction "A_1") (pintype "unspecified"))
      (node (ref "KEYS13") (pin "4") (pinfunction "4_4") (pintype "unspecified"))
    )
    (net (code "84") (name "Net-(D53-A)") (class "Default")
      (node (ref "D53") (pin "1") (pinfunction "A_1") (pintype "unspecified"))
      (node (ref "KEYS14") (pin "1") (pinfunction "1_1") (pintype "unspecified"))
    )
    (net (code "85") (name "Net-(D54-A)") (class "Default")
      (node (ref "D54") (pin "1") (pinfunction "A_1") (pintype "unspecified"))
      (node (ref "KEYS14") (pin "2") (pinfunction "2_2") (pintype "unspecified"))
    )
    (net (code "86") (name "Net-(D55-A)") (class "Default")
      (node (ref "D55") (pin "1") (pinfunction "A_1") (pintype "unspecified"))
      (node (ref "KEYS14") (pin "3") (pinfunction "3_3") (pintype "unspecified"))
    )
    (net (code "87") (name "Net-(D56-A)") (class "Default")
      (node (ref "D56") (pin "1") (pinfunction "A_1") (pintype "unspecified"))
      (node (ref "KEYS14") (pin "4") (pinfunction "4_4") (pintype "unspecified"))
    )
    (net (code "88") (name "Net-(D57-A)") (class "Default")
      (node (ref "D57") (pin "1") (pinfunction "A_1") (pintype "unspecified"))
      (node (ref "KEYS15") (pin "1") (pinfunction "1_1") (pintype "unspecified"))
    )
    (net (code "89") (name "Net-(D58-A)") (class "Default")
      (node (ref "D58") (pin "1") (pinfunction "A_1") (pintype "unspecified"))
      (node (ref "KEYS15") (pin "2") (pinfunction "2_2") (pintype "unspecified"))
    )
    (net (code "90") (name "Net-(D59-A)") (class "Default")
      (node (ref "D59") (pin "1") (pinfunction "A_1") (pintype "unspecified"))
      (node (ref "KEYS15") (pin "3") (pinfunction "3_3") (pintype "unspecified"))
    )
    (net (code "91") (name "Net-(D60-A)") (class "Default")
      (node (ref "D60") (pin "1") (pinfunction "A_1") (pintype "unspecified"))
      (node (ref "KEYS15") (pin "4") (pinfunction "4_4") (pintype "unspecified"))
    )
    (net (code "92") (name "Net-(D61-A)") (class "Default")
      (node (ref "D61") (pin "1") (pinfunction "A_1") (pintype "unspecified"))
      (node (ref "KEYS16") (pin "4") (pinfunction "4_4") (pintype "unspecified"))
    )
    (net (code "93") (name "Net-(D62-A)") (class "Default")
      (node (ref "D62") (pin "1") (pinfunction "A_1") (pintype "unspecified"))
      (node (ref "KEYS16") (pin "3") (pinfunction "3_3") (pintype "unspecified"))
    )
    (net (code "94") (name "Net-(D63-A)") (class "Default")
      (node (ref "D63") (pin "1") (pinfunction "A_1") (pintype "unspecified"))
      (node (ref "KEYS16") (pin "2") (pinfunction "2_2") (pintype "unspecified"))
    )
    (net (code "95") (name "Net-(D64-A)") (class "Default")
      (node (ref "D64") (pin "1") (pinfunction "A_1") (pintype "unspecified"))
      (node (ref "KEYS16") (pin "1") (pinfunction "1_1") (pintype "unspecified"))
    )
    (net (code "96") (name "Net-(D65-C)") (class "Default")
      (node (ref "D65") (pin "2") (pinfunction "C_2") (pintype "unspecified"))
      (node (ref "D66") (pin "2") (pinfunction "C_2") (pintype "unspecified"))
      (node (ref "D67") (pin "2") (pinfunction "C_2") (pintype "unspecified"))
      (node (ref "D68") (pin "2") (pinfunction "C_2") (pintype "unspecified"))
      (node (ref "IC17") (pin "2") (pinfunction "1D_2") (pintype "unspecified"))
      (node (ref "R26") (pin "1") (pinfunction "1_1") (pintype "input"))
    )
    (net (code "97") (name "Net-(D69-C)") (class "Default")
      (node (ref "C4") (pin "1") (pinfunction "1_1") (pintype "unspecified"))
      (node (ref "C8") (pin "2") (pinfunction "2_2") (pintype "unspecified"))
      (node (ref "D69") (pin "2") (pinfunction "C_2") (pintype "unspecified"))
      (node (ref "F1") (pin "2") (pinfunction "2_2") (pintype "unspecified"))
      (node (ref "KEY1") (pin "1") (pinfunction "1_1") (pintype "unspecified"))
      (node (ref "U1") (pin "2") (pinfunction "+_2") (pintype "unspecified"))
    )
    (net (code "98") (name "Net-(FLG--)") (class "Default")
      (node (ref "FLG") (pin "1") (pinfunction "-_1") (pintype "unspecified"))
      (node (ref "R36") (pin "2") (pinfunction "2_2") (pintype "input"))
    )
    (net (code "99") (name "Net-(IC1-A0)") (class "Default")
      (node (ref "IC1") (pin "1") (pinfunction "A0_1") (pintype "unspecified"))
      (node (ref "IC2") (pin "1") (pinfunction "A0_1") (pintype "unspecified"))
      (node (ref "IC3") (pin "14") (pinfunction "Q0_14") (pintype "unspecified"))
    )
    (net (code "100") (name "Net-(IC1-A1)") (class "Default")
      (node (ref "IC1") (pin "2") (pinfunction "A1_2") (pintype "unspecified"))
      (node (ref "IC2") (pin "2") (pinfunction "A1_2") (pintype "unspecified"))
      (node (ref "IC3") (pin "13") (pinfunction "Q1_13") (pintype "unspecified"))
    )
    (net (code "101") (name "Net-(IC1-A2)") (class "Default")
      (node (ref "IC1") (pin "3") (pinfunction "A2_3") (pintype "unspecified"))
      (node (ref "IC2") (pin "3") (pinfunction "A2_3") (pintype "unspecified"))
      (node (ref "IC3") (pin "12") (pinfunction "Q2_12") (pintype "unspecified"))
    )
    (net (code "102") (name "Net-(IC1-Y0)") (class "Default")
      (node (ref "IC1") (pin "15") (pinfunction "Y0_15") (pintype "unspecified"))
      (node (ref "KEYS1") (pin "5") (pinfunction "5_5") (pintype "unspecified"))
      (node (ref "KEYS1") (pin "6") (pinfunction "6_6") (pintype "unspecified"))
      (node (ref "KEYS1") (pin "7") (pinfunction "7_7") (pintype "unspecified"))
      (node (ref "KEYS1") (pin "8") (pinfunction "8_8") (pintype "unspecified"))
    )
    (net (code "103") (name "Net-(IC1-Y1)") (class "Default")
      (node (ref "IC1") (pin "14") (pinfunction "Y1_14") (pintype "unspecified"))
      (node (ref "KEYS2") (pin "5") (pinfunction "5_5") (pintype "unspecified"))
      (node (ref "KEYS2") (pin "6") (pinfunction "6_6") (pintype "unspecified"))
      (node (ref "KEYS2") (pin "7") (pinfunction "7_7") (pintype "unspecified"))
      (node (ref "KEYS2") (pin "8") (pinfunction "8_8") (pintype "unspecified"))
    )
    (net (code "104") (name "Net-(IC1-Y2)") (class "Default")
      (node (ref "IC1") (pin "13") (pinfunction "Y2_13") (pintype "unspecified"))
      (node (ref "KEYS3") (pin "5") (pinfunction "5_5") (pintype "unspecified"))
      (node (ref "KEYS3") (pin "6") (pinfunction "6_6") (pintype "unspecified"))
      (node (ref "KEYS3") (pin "7") (pinfunction "7_7") (pintype "unspecified"))
      (node (ref "KEYS3") (pin "8") (pinfunction "8_8") (pintype "unspecified"))
    )
    (net (code "105") (name "Net-(IC1-Y3)") (class "Default")
      (node (ref "IC1") (pin "12") (pinfunction "Y3_12") (pintype "unspecified"))
      (node (ref "KEYS4") (pin "5") (pinfunction "5_5") (pintype "unspecified"))
      (node (ref "KEYS4") (pin "6") (pinfunction "6_6") (pintype "unspecified"))
      (node (ref "KEYS4") (pin "7") (pinfunction "7_7") (pintype "unspecified"))
      (node (ref "KEYS4") (pin "8") (pinfunction "8_8") (pintype "unspecified"))
    )
    (net (code "106") (name "Net-(IC1-Y4)") (class "Default")
      (node (ref "IC1") (pin "11") (pinfunction "Y4_11") (pintype "unspecified"))
      (node (ref "KEYS8") (pin "5") (pinfunction "5_5") (pintype "unspecified"))
      (node (ref "KEYS8") (pin "6") (pinfunction "6_6") (pintype "unspecified"))
      (node (ref "KEYS8") (pin "7") (pinfunction "7_7") (pintype "unspecified"))
      (node (ref "KEYS8") (pin "8") (pinfunction "8_8") (pintype "unspecified"))
    )
    (net (code "107") (name "Net-(IC1-Y5)") (class "Default")
      (node (ref "IC1") (pin "10") (pinfunction "Y5_10") (pintype "unspecified"))
      (node (ref "KEYS7") (pin "5") (pinfunction "5_5") (pintype "unspecified"))
      (node (ref "KEYS7") (pin "6") (pinfunction "6_6") (pintype "unspecified"))
      (node (ref "KEYS7") (pin "7") (pinfunction "7_7") (pintype "unspecified"))
      (node (ref "KEYS7") (pin "8") (pinfunction "8_8") (pintype "unspecified"))
    )
    (net (code "108") (name "Net-(IC1-Y6)") (class "Default")
      (node (ref "IC1") (pin "9") (pinfunction "Y6_9") (pintype "unspecified"))
      (node (ref "KEYS6") (pin "5") (pinfunction "5_5") (pintype "unspecified"))
      (node (ref "KEYS6") (pin "6") (pinfunction "6_6") (pintype "unspecified"))
      (node (ref "KEYS6") (pin "7") (pinfunction "7_7") (pintype "unspecified"))
      (node (ref "KEYS6") (pin "8") (pinfunction "8_8") (pintype "unspecified"))
    )
    (net (code "109") (name "Net-(IC1-Y7)") (class "Default")
      (node (ref "IC1") (pin "7") (pinfunction "Y7_7") (pintype "unspecified"))
      (node (ref "KEYS5") (pin "5") (pinfunction "5_5") (pintype "unspecified"))
      (node (ref "KEYS5") (pin "6") (pinfunction "6_6") (pintype "unspecified"))
      (node (ref "KEYS5") (pin "7") (pinfunction "7_7") (pintype "unspecified"))
      (node (ref "KEYS5") (pin "8") (pinfunction "8_8") (pintype "unspecified"))
    )
    (net (code "110") (name "Net-(IC1-nE1)") (class "Default")
      (node (ref "IC1") (pin "4") (pinfunction "nE1_4") (pintype "unspecified"))
      (node (ref "IC1") (pin "5") (pinfunction "nE2_5") (pintype "unspecified"))
      (node (ref "IC2") (pin "6") (pinfunction "E3_6") (pintype "unspecified"))
      (node (ref "IC3") (pin "11") (pinfunction "Q3_11") (pintype "unspecified"))
    )
    (net (code "111") (name "Net-(IC2-Y0)") (class "Default")
      (node (ref "IC2") (pin "15") (pinfunction "Y0_15") (pintype "unspecified"))
      (node (ref "KEYS12") (pin "5") (pinfunction "5_5") (pintype "unspecified"))
      (node (ref "KEYS12") (pin "6") (pinfunction "6_6") (pintype "unspecified"))
      (node (ref "KEYS12") (pin "7") (pinfunction "7_7") (pintype "unspecified"))
      (node (ref "KEYS12") (pin "8") (pinfunction "8_8") (pintype "unspecified"))
    )
    (net (code "112") (name "Net-(IC2-Y1)") (class "Default")
      (node (ref "IC2") (pin "14") (pinfunction "Y1_14") (pintype "unspecified"))
      (node (ref "KEYS11") (pin "5") (pinfunction "5_5") (pintype "unspecified"))
      (node (ref "KEYS11") (pin "6") (pinfunction "6_6") (pintype "unspecified"))
      (node (ref "KEYS11") (pin "7") (pinfunction "7_7") (pintype "unspecified"))
      (node (ref "KEYS11") (pin "8") (pinfunction "8_8") (pintype "unspecified"))
    )
    (net (code "113") (name "Net-(IC2-Y2)") (class "Default")
      (node (ref "IC2") (pin "13") (pinfunction "Y2_13") (pintype "unspecified"))
      (node (ref "KEYS10") (pin "5") (pinfunction "5_5") (pintype "unspecified"))
      (node (ref "KEYS10") (pin "6") (pinfunction "6_6") (pintype "unspecified"))
      (node (ref "KEYS10") (pin "7") (pinfunction "7_7") (pintype "unspecified"))
      (node (ref "KEYS10") (pin "8") (pinfunction "8_8") (pintype "unspecified"))
    )
    (net (code "114") (name "Net-(IC2-Y3)") (class "Default")
      (node (ref "IC2") (pin "12") (pinfunction "Y3_12") (pintype "unspecified"))
      (node (ref "KEYS9") (pin "5") (pinfunction "5_5") (pintype "unspecified"))
      (node (ref "KEYS9") (pin "6") (pinfunction "6_6") (pintype "unspecified"))
      (node (ref "KEYS9") (pin "7") (pinfunction "7_7") (pintype "unspecified"))
      (node (ref "KEYS9") (pin "8") (pinfunction "8_8") (pintype "unspecified"))
    )
    (net (code "115") (name "Net-(IC2-Y4)") (class "Default")
      (node (ref "IC2") (pin "11") (pinfunction "Y4_11") (pintype "unspecified"))
      (node (ref "KEYS16") (pin "5") (pinfunction "5_5") (pintype "unspecified"))
      (node (ref "KEYS16") (pin "6") (pinfunction "6_6") (pintype "unspecified"))
      (node (ref "KEYS16") (pin "7") (pinfunction "7_7") (pintype "unspecified"))
      (node (ref "KEYS16") (pin "8") (pinfunction "8_8") (pintype "unspecified"))
    )
    (net (code "116") (name "Net-(IC2-Y5)") (class "Default")
      (node (ref "IC2") (pin "10") (pinfunction "Y5_10") (pintype "unspecified"))
      (node (ref "KEYS15") (pin "5") (pinfunction "5_5") (pintype "unspecified"))
      (node (ref "KEYS15") (pin "6") (pinfunction "6_6") (pintype "unspecified"))
      (node (ref "KEYS15") (pin "7") (pinfunction "7_7") (pintype "unspecified"))
      (node (ref "KEYS15") (pin "8") (pinfunction "8_8") (pintype "unspecified"))
    )
    (net (code "117") (name "Net-(IC2-Y6)") (class "Default")
      (node (ref "IC2") (pin "9") (pinfunction "Y6_9") (pintype "unspecified"))
      (node (ref "KEYS14") (pin "5") (pinfunction "5_5") (pintype "unspecified"))
      (node (ref "KEYS14") (pin "6") (pinfunction "6_6") (pintype "unspecified"))
      (node (ref "KEYS14") (pin "7") (pinfunction "7_7") (pintype "unspecified"))
      (node (ref "KEYS14") (pin "8") (pinfunction "8_8") (pintype "unspecified"))
    )
    (net (code "118") (name "Net-(IC2-Y7)") (class "Default")
      (node (ref "IC2") (pin "7") (pinfunction "Y7_7") (pintype "unspecified"))
      (node (ref "KEYS13") (pin "5") (pinfunction "5_5") (pintype "unspecified"))
      (node (ref "KEYS13") (pin "6") (pinfunction "6_6") (pintype "unspecified"))
      (node (ref "KEYS13") (pin "7") (pinfunction "7_7") (pintype "unspecified"))
      (node (ref "KEYS13") (pin "8") (pinfunction "8_8") (pintype "unspecified"))
    )
    (net (code "119") (name "Net-(IC4-1B)") (class "Default")
      (node (ref "IC4") (pin "2") (pinfunction "1B_2") (pintype "unspecified"))
      (node (ref "IC5") (pin "5") (pinfunction "1Q_5") (pintype "unspecified"))
    )
    (net (code "120") (name "Net-(IC4-1Y)") (class "Default")
      (node (ref "IC4") (pin "3") (pinfunction "1Y_3") (pintype "unspecified"))
      (node (ref "IC4") (pin "4") (pinfunction "2A_4") (pintype "unspecified"))
      (node (ref "IC4") (pin "5") (pinfunction "2B_5") (pintype "unspecified"))
    )
    (net (code "121") (name "Net-(IC4-3A)") (class "Default")
      (node (ref "IC4") (pin "10") (pinfunction "3B_10") (pintype "unspecified"))
      (node (ref "IC4") (pin "11") (pinfunction "4Y_11") (pintype "unspecified"))
      (node (ref "IC4") (pin "9") (pinfunction "3A_9") (pintype "unspecified"))
    )
    (net (code "122") (name "Net-(IC4-4B)") (class "Default")
      (node (ref "IC4") (pin "13") (pinfunction "4B_13") (pintype "unspecified"))
      (node (ref "IC5") (pin "8") (pinfunction "2nQ_8") (pintype "unspecified"))
      (node (ref "IC7") (pin "1") (pinfunction "SLC_1") (pintype "unspecified"))
    )
    (net (code "123") (name "Net-(IC11-1Y)") (class "Default")
      (node (ref "IC11") (pin "3") (pinfunction "1Y_3") (pintype "unspecified"))
      (node (ref "IC9") (pin "2") (pinfunction "B2_2") (pintype "unspecified"))
    )
    (net (code "124") (name "Net-(IC11-2Y)") (class "Default")
      (node (ref "IC11") (pin "6") (pinfunction "2Y_6") (pintype "unspecified"))
      (node (ref "IC9") (pin "6") (pinfunction "B1_6") (pintype "unspecified"))
    )
    (net (code "125") (name "Net-(IC11-3Y)") (class "Default")
      (node (ref "IC11") (pin "8") (pinfunction "3Y_8") (pintype "unspecified"))
      (node (ref "IC9") (pin "12") (pinfunction "A4_12") (pintype "unspecified"))
    )
    (net (code "126") (name "Net-(IC11-4Y)") (class "Default")
      (node (ref "IC11") (pin "11") (pinfunction "4Y_11") (pintype "unspecified"))
      (node (ref "IC9") (pin "15") (pinfunction "B3_15") (pintype "unspecified"))
    )
    (net (code "127") (name "Net-(IC12-P0)") (class "Default")
      (node (ref "IC12") (pin "3") (pinfunction "P0_3") (pintype "unspecified"))
      (node (ref "IC15") (pin "7") (pinfunction "OUTA_7") (pintype "unspecified"))
    )
    (net (code "128") (name "Net-(IC12-P1)") (class "Default")
      (node (ref "IC12") (pin "4") (pinfunction "P1_4") (pintype "unspecified"))
      (node (ref "IC15") (pin "9") (pinfunction "OUTB_9") (pintype "unspecified"))
    )
    (net (code "129") (name "Net-(IC12-P2)") (class "Default")
      (node (ref "IC12") (pin "5") (pinfunction "P2_5") (pintype "unspecified"))
      (node (ref "IC16") (pin "7") (pinfunction "OUTA_7") (pintype "unspecified"))
    )
    (net (code "130") (name "Net-(IC12-P3)") (class "Default")
      (node (ref "IC12") (pin "6") (pinfunction "P3_6") (pintype "unspecified"))
      (node (ref "IC16") (pin "9") (pinfunction "OUTB_9") (pintype "unspecified"))
    )
    (net (code "131") (name "Net-(IC13-Q0)") (class "Default")
      (node (ref "IC13") (pin "14") (pinfunction "Q0_14") (pintype "unspecified"))
      (node (ref "IC14") (pin "1") (pinfunction "A0_1") (pintype "unspecified"))
    )
    (net (code "132") (name "Net-(IC13-Q1)") (class "Default")
      (node (ref "IC13") (pin "13") (pinfunction "Q1_13") (pintype "unspecified"))
      (node (ref "IC14") (pin "15") (pinfunction "A1_15") (pintype "unspecified"))
    )
    (net (code "133") (name "Net-(IC13-Q2)") (class "Default")
      (node (ref "IC13") (pin "12") (pinfunction "Q2_12") (pintype "unspecified"))
      (node (ref "IC14") (pin "14") (pinfunction "A2_14") (pintype "unspecified"))
    )
    (net (code "134") (name "Net-(IC13-Q3)") (class "Default")
      (node (ref "IC13") (pin "11") (pinfunction "Q3_11") (pintype "unspecified"))
      (node (ref "IC14") (pin "13") (pinfunction "A3_13") (pintype "unspecified"))
    )
    (net (code "135") (name "Net-(IC18-A-Pad9)") (class "Default")
      (node (ref "IC18") (pin "9") (pinfunction "A_9") (pintype "unspecified"))
      (node (ref "R15") (pin "1") (pinfunction "1_1") (pintype "unspecified"))
    )
    (net (code "136") (name "Net-(IC18-B-Pad10)") (class "Default")
      (node (ref "IC18") (pin "10") (pinfunction "B_10") (pintype "unspecified"))
      (node (ref "R16") (pin "1") (pinfunction "1_1") (pintype "unspecified"))
    )
    (net (code "137") (name "Net-(IC18-C-Pad11)") (class "Default")
      (node (ref "IC18") (pin "11") (pinfunction "C_11") (pintype "unspecified"))
      (node (ref "R17") (pin "1") (pinfunction "1_1") (pintype "unspecified"))
    )
    (net (code "138") (name "Net-(IC18-D-Pad12)") (class "Default")
      (node (ref "IC18") (pin "12") (pinfunction "D_12") (pintype "unspecified"))
      (node (ref "R18") (pin "1") (pinfunction "1_1") (pintype "unspecified"))
    )
    (net (code "139") (name "Net-(IC18-E)") (class "Default")
      (node (ref "IC18") (pin "13") (pinfunction "E_13") (pintype "unspecified"))
      (node (ref "R19") (pin "1") (pinfunction "1_1") (pintype "unspecified"))
    )
    (net (code "140") (name "Net-(IC18-F)") (class "Default")
      (node (ref "IC18") (pin "15") (pinfunction "F_15") (pintype "unspecified"))
      (node (ref "R20") (pin "1") (pinfunction "1_1") (pintype "unspecified"))
    )
    (net (code "141") (name "Net-(IC18-G)") (class "Default")
      (node (ref "IC18") (pin "14") (pinfunction "G_14") (pintype "unspecified"))
      (node (ref "R21") (pin "1") (pinfunction "1_1") (pintype "unspecified"))
    )
    (net (code "142") (name "Net-(IC19-1A)") (class "Default")
      (node (ref "C2") (pin "2") (pinfunction "2_2") (pintype "unspecified"))
      (node (ref "IC19") (pin "1") (pinfunction "1A_1") (pintype "unspecified"))
      (node (ref "R8") (pin "1") (pinfunction "1_1") (pintype "input"))
      (node (ref "RST") (pin "1") (pinfunction "1_1") (pintype "unspecified"))
      (node (ref "RST") (pin "2") (pinfunction "2_2") (pintype "unspecified"))
    )
    (net (code "143") (name "Net-(IC19-1Y)") (class "Default")
      (node (ref "IC19") (pin "2") (pinfunction "1Y_2") (pintype "unspecified"))
      (node (ref "IC19") (pin "3") (pinfunction "2A_3") (pintype "unspecified"))
    )
    (net (code "144") (name "Net-(IC19-3A)") (class "Default")
      (node (ref "C3") (pin "2") (pinfunction "2_2") (pintype "unspecified"))
      (node (ref "IC19") (pin "5") (pinfunction "3A_5") (pintype "unspecified"))
      (node (ref "R5") (pin "2") (pinfunction "2_2") (pintype "input"))
      (node (ref "R5") (pin "3") (pinfunction "3_3") (pintype "input"))
    )
    (net (code "145") (name "Net-(IC19-3Y)") (class "Default")
      (node (ref "H1") (pin "1") (pinfunction "1_1") (pintype "unspecified"))
      (node (ref "IC19") (pin "6") (pinfunction "3Y_6") (pintype "unspecified"))
      (node (ref "R11") (pin "2") (pinfunction "2_2") (pintype "unspecified"))
    )
    (net (code "146") (name "Net-(IC19-4A)") (class "Default")
      (node (ref "C1") (pin "1") (pinfunction "1_1") (pintype "unspecified"))
      (node (ref "CLOCK") (pin "1") (pinfunction "1_1") (pintype "unspecified"))
      (node (ref "CLOCK") (pin "2") (pinfunction "2_2") (pintype "unspecified"))
      (node (ref "IC19") (pin "13") (pinfunction "4A_13") (pintype "unspecified"))
      (node (ref "R9") (pin "1") (pinfunction "1_1") (pintype "input"))
    )
    (net (code "147") (name "Net-(IC19-4Y)") (class "Default")
      (node (ref "H1") (pin "3") (pinfunction "3_3") (pintype "unspecified"))
      (node (ref "IC19") (pin "12") (pinfunction "4Y_12") (pintype "unspecified"))
    )
    (net (code "148") (name "Net-(IC19-5A)") (class "Default")
      (node (ref "H1") (pin "2") (pinfunction "2_2") (pintype "unspecified"))
      (node (ref "IC19") (pin "11") (pinfunction "5A_11") (pintype "unspecified"))
      (node (ref "IC4") (pin "1") (pinfunction "1A_1") (pintype "unspecified"))
    )
    (net (code "149") (name "Net-(IC19-5Y)") (class "Default")
      (node (ref "IC19") (pin "10") (pinfunction "5Y_10") (pintype "unspecified"))
      (node (ref "IC5") (pin "3") (pinfunction "1CK_3") (pintype "unspecified"))
    )
    (net (code "150") (name "Net-(IC19-6A)") (class "Default")
      (node (ref "IC19") (pin "9") (pinfunction "6A_9") (pintype "unspecified"))
      (node (ref "IC4") (pin "6") (pinfunction "2Y_6") (pintype "unspecified"))
      (node (ref "R14") (pin "1") (pinfunction "1_1") (pintype "input"))
      (node (ref "R42") (pin "1") (pinfunction "1_1") (pintype "input"))
    )
    (net (code "151") (name "Net-(OUT--)") (class "Default")
      (node (ref "OUT") (pin "1") (pinfunction "-_1") (pintype "unspecified"))
      (node (ref "R40") (pin "2") (pinfunction "2_2") (pintype "input"))
    )
    (net (code "152") (name "Net-(PC-+)") (class "Default")
      (node (ref "PC") (pin "2") (pinfunction "+_2") (pintype "unspecified"))
      (node (ref "R35") (pin "2") (pinfunction "2_2") (pintype "input"))
    )
    (net (code "153") (name "Net-(R11-Pad1)") (class "Default")
      (node (ref "R11") (pin "1") (pinfunction "1_1") (pintype "unspecified"))
      (node (ref "R5") (pin "1") (pinfunction "1_1") (pintype "input"))
    )
    (net (code "154") (name "Net-(REG-+)") (class "Default")
      (node (ref "R38") (pin "2") (pinfunction "2_2") (pintype "input"))
      (node (ref "REG") (pin "2") (pinfunction "+_2") (pintype "unspecified"))
    )
    (net (code "155") (name "Net-(ROM0-+)") (class "Default")
      (node (ref "R27") (pin "1") (pinfunction "1_1") (pintype "input"))
      (node (ref "ROM0") (pin "2") (pinfunction "+_2") (pintype "unspecified"))
    )
    (net (code "156") (name "Net-(ROM1-+)") (class "Default")
      (node (ref "R28") (pin "1") (pinfunction "1_1") (pintype "input"))
      (node (ref "ROM1") (pin "2") (pinfunction "+_2") (pintype "unspecified"))
    )
    (net (code "157") (name "Net-(ROM2-+)") (class "Default")
      (node (ref "R29") (pin "1") (pinfunction "1_1") (pintype "input"))
      (node (ref "ROM2") (pin "2") (pinfunction "+_2") (pintype "unspecified"))
    )
    (net (code "158") (name "Net-(ROM3-+)") (class "Default")
      (node (ref "R30") (pin "1") (pinfunction "1_1") (pintype "input"))
      (node (ref "ROM3") (pin "2") (pinfunction "+_2") (pintype "unspecified"))
    )
    (net (code "159") (name "Net-(U1--)") (class "Default")
      (node (ref "R12") (pin "2") (pinfunction "2_2") (pintype "input"))
      (node (ref "U1") (pin "1") (pinfunction "-_1") (pintype "unspecified"))
    )
    (net (code "160") (name "Net-(U2--)") (class "Default")
      (node (ref "R42") (pin "2") (pinfunction "2_2") (pintype "input"))
      (node (ref "U2") (pin "1") (pinfunction "-_1") (pintype "unspecified"))
    )
    (net (code "161") (name "Net-(USB-VCC)") (class "Default")
      (node (ref "F1") (pin "1") (pinfunction "1_1") (pintype "unspecified"))
      (node (ref "USB") (pin "1") (pinfunction "VCC_1") (pintype "unspecified"))
    )
    (net (code "162") (name "OUT") (class "Default")
      (node (ref "IC18") (pin "1") (pinfunction "LCH_1") (pintype "unspecified"))
      (node (ref "IC8") (pin "13") (pinfunction "I/O_13") (pintype "unspecified"))
      (node (ref "OUT") (pin "2") (pinfunction "+_2") (pintype "unspecified"))
    )
    (net (code "163") (name "PCLD") (class "Default")
      (node (ref "IC3") (pin "9") (pinfunction "nLOAD_9") (pintype "unspecified"))
      (node (ref "IC8") (pin "19") (pinfunction "I/O_19") (pintype "unspecified"))
      (node (ref "PC") (pin "1") (pinfunction "-_1") (pintype "unspecified"))
    )
    (net (code "164") (name "REG0") (class "Default")
      (node (ref "IC11") (pin "4") (pinfunction "2A_4") (pintype "unspecified"))
      (node (ref "IC14") (pin "5") (pinfunction "Q2_5") (pintype "unspecified"))
      (node (ref "IC15") (pin "4") (pinfunction "A2_4") (pintype "unspecified"))
      (node (ref "R1") (pin "1") (pinfunction "1_1") (pintype "input"))
    )
    (net (code "165") (name "REG1") (class "Default")
      (node (ref "IC11") (pin "1") (pinfunction "1A_1") (pintype "unspecified"))
      (node (ref "IC14") (pin "11") (pinfunction "Q4_11") (pintype "unspecified"))
      (node (ref "IC15") (pin "12") (pinfunction "B2_12") (pintype "unspecified"))
      (node (ref "R2") (pin "1") (pinfunction "1_1") (pintype "input"))
    )
    (net (code "166") (name "REG2") (class "Default")
      (node (ref "IC11") (pin "13") (pinfunction "4B_13") (pintype "unspecified"))
      (node (ref "IC14") (pin "7") (pinfunction "Q1_7") (pintype "unspecified"))
      (node (ref "IC16") (pin "4") (pinfunction "A2_4") (pintype "unspecified"))
      (node (ref "R3") (pin "1") (pinfunction "1_1") (pintype "input"))
    )
    (net (code "167") (name "REG3") (class "Default")
      (node (ref "IC11") (pin "10") (pinfunction "3B_10") (pintype "unspecified"))
      (node (ref "IC14") (pin "9") (pinfunction "Q3_9") (pintype "unspecified"))
      (node (ref "IC16") (pin "12") (pinfunction "B2_12") (pintype "unspecified"))
      (node (ref "R4") (pin "1") (pinfunction "1_1") (pintype "input"))
    )
    (net (code "168") (name "REGWR") (class "Default")
      (node (ref "IC14") (pin "3") (pinfunction "#RW_3") (pintype "unspecified"))
      (node (ref "IC8") (pin "16") (pinfunction "O_16") (pintype "unspecified"))
      (node (ref "REG") (pin "1") (pinfunction "-_1") (pintype "unspecified"))
    )
    (net (code "169") (name "ROM0") (class "Default")
      (node (ref "D13") (pin "2") (pinfunction "C_2") (pintype "unspecified"))
      (node (ref "D20") (pin "2") (pinfunction "C_2") (pintype "unspecified"))
      (node (ref "D24") (pin "2") (pinfunction "C_2") (pintype "unspecified"))
      (node (ref "D28") (pin "2") (pinfunction "C_2") (pintype "unspecified"))
      (node (ref "D29") (pin "2") (pinfunction "C_2") (pintype "unspecified"))
      (node (ref "D36") (pin "2") (pinfunction "C_2") (pintype "unspecified"))
      (node (ref "D4") (pin "2") (pinfunction "C_2") (pintype "unspecified"))
      (node (ref "D40") (pin "2") (pinfunction "C_2") (pintype "unspecified"))
      (node (ref "D44") (pin "2") (pinfunction "C_2") (pintype "unspecified"))
      (node (ref "D45") (pin "2") (pinfunction "C_2") (pintype "unspecified"))
      (node (ref "D5") (pin "2") (pinfunction "C_2") (pintype "unspecified"))
      (node (ref "D52") (pin "2") (pinfunction "C_2") (pintype "unspecified"))
      (node (ref "D56") (pin "2") (pinfunction "C_2") (pintype "unspecified"))
      (node (ref "D60") (pin "2") (pinfunction "C_2") (pintype "unspecified"))
      (node (ref "D61") (pin "2") (pinfunction "C_2") (pintype "unspecified"))
      (node (ref "D9") (pin "2") (pinfunction "C_2") (pintype "unspecified"))
      (node (ref "IC13") (pin "3") (pinfunction "P0_3") (pintype "unspecified"))
      (node (ref "IC15") (pin "6") (pinfunction "A0_6") (pintype "unspecified"))
      (node (ref "IC3") (pin "3") (pinfunction "P0_3") (pintype "unspecified"))
      (node (ref "IC6") (pin "6") (pinfunction "P3_6") (pintype "unspecified"))
      (node (ref "IC7") (pin "3") (pinfunction "1B_3") (pintype "unspecified"))
      (node (ref "R13") (pin "1") (pinfunction "1_1") (pintype "input"))
      (node (ref "R27") (pin "2") (pinfunction "2_2") (pintype "input"))
    )
    (net (code "170") (name "ROM1") (class "Default")
      (node (ref "D10") (pin "2") (pinfunction "C_2") (pintype "unspecified"))
      (node (ref "D14") (pin "2") (pinfunction "C_2") (pintype "unspecified"))
      (node (ref "D19") (pin "2") (pinfunction "C_2") (pintype "unspecified"))
      (node (ref "D23") (pin "2") (pinfunction "C_2") (pintype "unspecified"))
      (node (ref "D27") (pin "2") (pinfunction "C_2") (pintype "unspecified"))
      (node (ref "D3") (pin "2") (pinfunction "C_2") (pintype "unspecified"))
      (node (ref "D30") (pin "2") (pinfunction "C_2") (pintype "unspecified"))
      (node (ref "D35") (pin "2") (pinfunction "C_2") (pintype "unspecified"))
      (node (ref "D39") (pin "2") (pinfunction "C_2") (pintype "unspecified"))
      (node (ref "D43") (pin "2") (pinfunction "C_2") (pintype "unspecified"))
      (node (ref "D46") (pin "2") (pinfunction "C_2") (pintype "unspecified"))
      (node (ref "D51") (pin "2") (pinfunction "C_2") (pintype "unspecified"))
      (node (ref "D55") (pin "2") (pinfunction "C_2") (pintype "unspecified"))
      (node (ref "D59") (pin "2") (pinfunction "C_2") (pintype "unspecified"))
      (node (ref "D6") (pin "2") (pinfunction "C_2") (pintype "unspecified"))
      (node (ref "D62") (pin "2") (pinfunction "C_2") (pintype "unspecified"))
      (node (ref "IC13") (pin "4") (pinfunction "P1_4") (pintype "unspecified"))
      (node (ref "IC15") (pin "10") (pinfunction "B0_10") (pintype "unspecified"))
      (node (ref "IC3") (pin "4") (pinfunction "P1_4") (pintype "unspecified"))
      (node (ref "IC6") (pin "5") (pinfunction "P2_5") (pintype "unspecified"))
      (node (ref "IC7") (pin "13") (pinfunction "4B_13") (pintype "unspecified"))
      (node (ref "R10") (pin "1") (pinfunction "1_1") (pintype "input"))
      (node (ref "R28") (pin "2") (pinfunction "2_2") (pintype "input"))
    )
    (net (code "171") (name "ROM2") (class "Default")
      (node (ref "D11") (pin "2") (pinfunction "C_2") (pintype "unspecified"))
      (node (ref "D15") (pin "2") (pinfunction "C_2") (pintype "unspecified"))
      (node (ref "D18") (pin "2") (pinfunction "C_2") (pintype "unspecified"))
      (node (ref "D2") (pin "2") (pinfunction "C_2") (pintype "unspecified"))
      (node (ref "D22") (pin "2") (pinfunction "C_2") (pintype "unspecified"))
      (node (ref "D26") (pin "2") (pinfunction "C_2") (pintype "unspecified"))
      (node (ref "D31") (pin "2") (pinfunction "C_2") (pintype "unspecified"))
      (node (ref "D34") (pin "2") (pinfunction "C_2") (pintype "unspecified"))
      (node (ref "D38") (pin "2") (pinfunction "C_2") (pintype "unspecified"))
      (node (ref "D42") (pin "2") (pinfunction "C_2") (pintype "unspecified"))
      (node (ref "D47") (pin "2") (pinfunction "C_2") (pintype "unspecified"))
      (node (ref "D50") (pin "2") (pinfunction "C_2") (pintype "unspecified"))
      (node (ref "D54") (pin "2") (pinfunction "C_2") (pintype "unspecified"))
      (node (ref "D58") (pin "2") (pinfunction "C_2") (pintype "unspecified"))
      (node (ref "D63") (pin "2") (pinfunction "C_2") (pintype "unspecified"))
      (node (ref "D7") (pin "2") (pinfunction "C_2") (pintype "unspecified"))
      (node (ref "IC13") (pin "5") (pinfunction "P2_5") (pintype "unspecified"))
      (node (ref "IC16") (pin "6") (pinfunction "A0_6") (pintype "unspecified"))
      (node (ref "IC3") (pin "5") (pinfunction "P2_5") (pintype "unspecified"))
      (node (ref "IC6") (pin "4") (pinfunction "P1_4") (pintype "unspecified"))
      (node (ref "IC7") (pin "6") (pinfunction "2B_6") (pintype "unspecified"))
      (node (ref "R29") (pin "2") (pinfunction "2_2") (pintype "input"))
      (node (ref "R7") (pin "1") (pinfunction "1_1") (pintype "input"))
    )
    (net (code "172") (name "ROM3") (class "Default")
      (node (ref "D1") (pin "2") (pinfunction "C_2") (pintype "unspecified"))
      (node (ref "D12") (pin "2") (pinfunction "C_2") (pintype "unspecified"))
      (node (ref "D16") (pin "2") (pinfunction "C_2") (pintype "unspecified"))
      (node (ref "D17") (pin "2") (pinfunction "C_2") (pintype "unspecified"))
      (node (ref "D21") (pin "2") (pinfunction "C_2") (pintype "unspecified"))
      (node (ref "D25") (pin "2") (pinfunction "C_2") (pintype "unspecified"))
      (node (ref "D32") (pin "2") (pinfunction "C_2") (pintype "unspecified"))
      (node (ref "D33") (pin "2") (pinfunction "C_2") (pintype "unspecified"))
      (node (ref "D37") (pin "2") (pinfunction "C_2") (pintype "unspecified"))
      (node (ref "D41") (pin "2") (pinfunction "C_2") (pintype "unspecified"))
      (node (ref "D48") (pin "2") (pinfunction "C_2") (pintype "unspecified"))
      (node (ref "D49") (pin "2") (pinfunction "C_2") (pintype "unspecified"))
      (node (ref "D53") (pin "2") (pinfunction "C_2") (pintype "unspecified"))
      (node (ref "D57") (pin "2") (pinfunction "C_2") (pintype "unspecified"))
      (node (ref "D64") (pin "2") (pinfunction "C_2") (pintype "unspecified"))
      (node (ref "D8") (pin "2") (pinfunction "C_2") (pintype "unspecified"))
      (node (ref "IC13") (pin "6") (pinfunction "P3_6") (pintype "unspecified"))
      (node (ref "IC16") (pin "10") (pinfunction "B0_10") (pintype "unspecified"))
      (node (ref "IC3") (pin "6") (pinfunction "P3_6") (pintype "unspecified"))
      (node (ref "IC4") (pin "12") (pinfunction "4A_12") (pintype "unspecified"))
      (node (ref "IC6") (pin "3") (pinfunction "P0_3") (pintype "unspecified"))
      (node (ref "IC7") (pin "10") (pinfunction "3B_10") (pintype "unspecified"))
      (node (ref "R30") (pin "2") (pinfunction "2_2") (pintype "input"))
      (node (ref "R6") (pin "1") (pinfunction "1_1") (pintype "input"))
    )
    (net (code "173") (name "ROM4") (class "Default")
      (node (ref "IC6") (pin "11") (pinfunction "Q3_11") (pintype "unspecified"))
      (node (ref "IC7") (pin "2") (pinfunction "1A_2") (pintype "unspecified"))
    )
    (net (code "174") (name "ROM5") (class "Default")
      (node (ref "IC6") (pin "12") (pinfunction "Q2_12") (pintype "unspecified"))
      (node (ref "IC7") (pin "14") (pinfunction "4A_14") (pintype "unspecified"))
    )
    (net (code "175") (name "ROM6") (class "Default")
      (node (ref "IC6") (pin "13") (pinfunction "Q1_13") (pintype "unspecified"))
      (node (ref "IC7") (pin "5") (pinfunction "2A_5") (pintype "unspecified"))
    )
    (net (code "176") (name "ROM7") (class "Default")
      (node (ref "IC6") (pin "14") (pinfunction "Q0_14") (pintype "unspecified"))
      (node (ref "IC7") (pin "11") (pinfunction "3A_11") (pintype "unspecified"))
    )
    (net (code "177") (name "RST") (class "Default")
      (node (ref "IC12") (pin "1") (pinfunction "nCR_1") (pintype "unspecified"))
      (node (ref "IC13") (pin "1") (pinfunction "nCR_1") (pintype "unspecified"))
      (node (ref "IC17") (pin "1") (pinfunction "1CR_1") (pintype "unspecified"))
      (node (ref "IC17") (pin "13") (pinfunction "2CR_13") (pintype "unspecified"))
      (node (ref "IC19") (pin "4") (pinfunction "2Y_4") (pintype "unspecified"))
      (node (ref "IC3") (pin "1") (pinfunction "nCR_1") (pintype "unspecified"))
      (node (ref "IC5") (pin "1") (pinfunction "1CR_1") (pintype "unspecified"))
      (node (ref "IC5") (pin "13") (pinfunction "2CR_13") (pintype "unspecified"))
      (node (ref "IC6") (pin "1") (pinfunction "nCR_1") (pintype "unspecified"))
      (node (ref "IC8") (pin "6") (pinfunction "I_6") (pintype "unspecified"))
    )
    (net (code "178") (name "SEGA") (class "Default")
      (node (ref "LED1") (pin "7") (pinfunction "a_7") (pintype "input"))
      (node (ref "R15") (pin "2") (pinfunction "2_2") (pintype "unspecified"))
    )
    (net (code "179") (name "SEGB") (class "Default")
      (node (ref "LED1") (pin "6") (pinfunction "b_6") (pintype "input"))
      (node (ref "R16") (pin "2") (pinfunction "2_2") (pintype "unspecified"))
    )
    (net (code "180") (name "SEGC") (class "Default")
      (node (ref "LED1") (pin "4") (pinfunction "c_4") (pintype "input"))
      (node (ref "R17") (pin "2") (pinfunction "2_2") (pintype "unspecified"))
    )
    (net (code "181") (name "SEGD") (class "Default")
      (node (ref "LED1") (pin "2") (pinfunction "d_2") (pintype "input"))
      (node (ref "R18") (pin "2") (pinfunction "2_2") (pintype "unspecified"))
    )
    (net (code "182") (name "SEGE") (class "Default")
      (node (ref "LED1") (pin "1") (pinfunction "e_1") (pintype "input"))
      (node (ref "R19") (pin "2") (pinfunction "2_2") (pintype "unspecified"))
    )
    (net (code "183") (name "SEGF") (class "Default")
      (node (ref "LED1") (pin "9") (pinfunction "f_9") (pintype "input"))
      (node (ref "R20") (pin "2") (pinfunction "2_2") (pintype "unspecified"))
    )
    (net (code "184") (name "SEGG") (class "Default")
      (node (ref "LED1") (pin "10") (pinfunction "g_10") (pintype "input"))
      (node (ref "R21") (pin "2") (pinfunction "2_2") (pintype "unspecified"))
    )
    (net (code "185") (name "STATUS") (class "Default")
      (node (ref "IC4") (pin "8") (pinfunction "3Y_8") (pintype "unspecified"))
      (node (ref "IC5") (pin "12") (pinfunction "2D_12") (pintype "unspecified"))
      (node (ref "IC8") (pin "7") (pinfunction "I_7") (pintype "unspecified"))
      (node (ref "R*1") (pin "1") (pinfunction "1_1") (pintype "unspecified"))
    )
    (net (code "186") (name "VCC") (class "Default")
      (node (ref "C5") (pin "1") (pinfunction "1_1") (pintype "unspecified"))
      (node (ref "C6") (pin "1") (pinfunction "1_1") (pintype "unspecified"))
      (node (ref "C7") (pin "1") (pinfunction "1_1") (pintype "unspecified"))
      (node (ref "C8") (pin "1") (pinfunction "1_1") (pintype "unspecified"))
      (node (ref "IC1") (pin "16") (pinfunction "VCC_16") (pintype "unspecified"))
      (node (ref "IC1") (pin "6") (pinfunction "E3_6") (pintype "unspecified"))
      (node (ref "IC11") (pin "14") (pinfunction "VCC_14") (pintype "unspecified"))
      (node (ref "IC12") (pin "16") (pinfunction "VCC_16") (pintype "unspecified"))
      (node (ref "IC13") (pin "16") (pinfunction "VCC_16") (pintype "unspecified"))
      (node (ref "IC14") (pin "16") (pinfunction "VCC_16") (pintype "unspecified"))
      (node (ref "IC15") (pin "16") (pinfunction "VCC_16") (pintype "unspecified"))
      (node (ref "IC16") (pin "16") (pinfunction "VCC_16") (pintype "unspecified"))
      (node (ref "IC17") (pin "10") (pinfunction "2PR_10") (pintype "unspecified"))
      (node (ref "IC17") (pin "14") (pinfunction "VCC_14") (pintype "unspecified"))
      (node (ref "IC17") (pin "4") (pinfunction "1PR_4") (pintype "unspecified"))
      (node (ref "IC18") (pin "16") (pinfunction "VDD_16") (pintype "unspecified"))
      (node (ref "IC18") (pin "6") (pinfunction "PH_6") (pintype "unspecified"))
      (node (ref "IC19") (pin "14") (pinfunction "VCC_14") (pintype "unspecified"))
      (node (ref "IC2") (pin "16") (pinfunction "VCC_16") (pintype "unspecified"))
      (node (ref "IC3") (pin "10") (pinfunction "TE_10") (pintype "unspecified"))
      (node (ref "IC3") (pin "16") (pinfunction "VCC_16") (pintype "unspecified"))
      (node (ref "IC3") (pin "7") (pinfunction "PE_7") (pintype "unspecified"))
      (node (ref "IC4") (pin "14") (pinfunction "VCC_14") (pintype "unspecified"))
      (node (ref "IC5") (pin "10") (pinfunction "2PR_10") (pintype "unspecified"))
      (node (ref "IC5") (pin "14") (pinfunction "VCC_14") (pintype "unspecified"))
      (node (ref "IC5") (pin "2") (pinfunction "1D_2") (pintype "unspecified"))
      (node (ref "IC5") (pin "4") (pinfunction "1PR_4") (pintype "unspecified"))
      (node (ref "IC6") (pin "16") (pinfunction "VCC_16") (pintype "unspecified"))
      (node (ref "IC7") (pin "16") (pinfunction "VCC_16") (pintype "unspecified"))
      (node (ref "IC8") (pin "20") (pinfunction "VCC_20") (pintype "unspecified"))
      (node (ref "IC9") (pin "16") (pinfunction "VCC_16") (pintype "unspecified"))
      (node (ref "K0") (pin "1") (pinfunction "1_1") (pintype "unspecified"))
      (node (ref "K0") (pin "2") (pinfunction "2_2") (pintype "unspecified"))
      (node (ref "K1") (pin "1") (pinfunction "1_1") (pintype "unspecified"))
      (node (ref "K1") (pin "2") (pinfunction "2_2") (pintype "unspecified"))
      (node (ref "K2") (pin "1") (pinfunction "1_1") (pintype "unspecified"))
      (node (ref "K2") (pin "2") (pinfunction "2_2") (pintype "unspecified"))
      (node (ref "K3") (pin "1") (pinfunction "1_1") (pintype "unspecified"))
      (node (ref "K3") (pin "2") (pinfunction "2_2") (pintype "unspecified"))
      (node (ref "KEY1") (pin "2") (pinfunction "2_2") (pintype "unspecified"))
      (node (ref "KEY1") (pin "3") (pinfunction "3_3") (pintype "unspecified"))
      (node (ref "LED1") (pin "3") (pinfunction "G1_3") (pintype "input"))
      (node (ref "LED1") (pin "8") (pinfunction "G1_8") (pintype "input"))
      (node (ref "R*1") (pin "2") (pinfunction "2_2") (pintype "unspecified"))
      (node (ref "R1") (pin "2") (pinfunction "2_2") (pintype "input"))
      (node (ref "R14") (pin "2") (pinfunction "2_2") (pintype "input"))
      (node (ref "R2") (pin "2") (pinfunction "2_2") (pintype "input"))
      (node (ref "R3") (pin "2") (pinfunction "2_2") (pintype "input"))
      (node (ref "R35") (pin "1") (pinfunction "1_1") (pintype "input"))
      (node (ref "R37") (pin "1") (pinfunction "1_1") (pintype "input"))
      (node (ref "R38") (pin "1") (pinfunction "1_1") (pintype "input"))
      (node (ref "R39") (pin "1") (pinfunction "1_1") (pintype "input"))
      (node (ref "R4") (pin "2") (pinfunction "2_2") (pintype "input"))
      (node (ref "R8") (pin "2") (pinfunction "2_2") (pintype "input"))
      (node (ref "R9") (pin "2") (pinfunction "2_2") (pintype "input"))
      (node (ref "U2") (pin "2") (pinfunction "+_2") (pintype "unspecified"))
    )
    (net (code "187") (name "ZF") (class "Default")
      (node (ref "IC17") (pin "6") (pinfunction "1nQ_6") (pintype "unspecified"))
      (node (ref "IC8") (pin "9") (pinfunction "I_9") (pintype "unspecified"))
    )
    (net (code "188") (name "unconnected-(IC3-TC-Pad15)") (class "Default")
      (node (ref "IC3") (pin "15") (pinfunction "TC_15") (pintype "unspecified+no_connect"))
    )
    (net (code "189") (name "unconnected-(IC5-1nQ-Pad6)") (class "Default")
      (node (ref "IC5") (pin "6") (pinfunction "1nQ_6") (pintype "unspecified+no_connect"))
    )
    (net (code "190") (name "unconnected-(IC5-2Q-Pad9)") (class "Default")
      (node (ref "IC5") (pin "9") (pinfunction "2Q_9") (pintype "unspecified+no_connect"))
    )
    (net (code "191") (name "unconnected-(IC6-TC-Pad15)") (class "Default")
      (node (ref "IC6") (pin "15") (pinfunction "TC_15") (pintype "unspecified+no_connect"))
    )
    (net (code "192") (name "unconnected-(IC8-I{slash}#OE-Pad11)") (class "Default")
      (node (ref "IC8") (pin "11") (pinfunction "I/#OE_11") (pintype "unspecified+no_connect"))
    )
    (net (code "193") (name "unconnected-(IC8-I{slash}O-Pad14)") (class "Default")
      (node (ref "IC8") (pin "14") (pinfunction "I/O_14") (pintype "unspecified+no_connect"))
    )
    (net (code "194") (name "unconnected-(IC12-TC-Pad15)") (class "Default")
      (node (ref "IC12") (pin "15") (pinfunction "TC_15") (pintype "unspecified+no_connect"))
    )
    (net (code "195") (name "unconnected-(IC13-TC-Pad15)") (class "Default")
      (node (ref "IC13") (pin "15") (pinfunction "TC_15") (pintype "unspecified+no_connect"))
    )
    (net (code "196") (name "unconnected-(IC17-1Q-Pad5)") (class "Default")
      (node (ref "IC17") (pin "5") (pinfunction "1Q_5") (pintype "unspecified+no_connect"))
    )
    (net (code "197") (name "unconnected-(IC17-2nQ-Pad8)") (class "Default")
      (node (ref "IC17") (pin "8") (pinfunction "2nQ_8") (pintype "unspecified+no_connect"))
    )
    (net (code "198") (name "unconnected-(LED1-dp-Pad5)") (class "Default")
      (node (ref "LED1") (pin "5") (pinfunction "dp_5") (pintype "input+no_connect"))
    )
    (net (code "199") (name "unconnected-(USB-EP-Pad3)") (class "Default")
      (node (ref "USB") (pin "3") (pinfunction "EP_3") (pintype "unspecified+no_connect"))
    )
    (net (code "200") (name "unconnected-(USB-EP-Pad4)") (class "Default")
      (node (ref "USB") (pin "4") (pinfunction "EP_4") (pintype "unspecified+no_connect"))
    )
  )
)
